# slot1.net
KiCad netlist of a schematic drawn in EAGLE
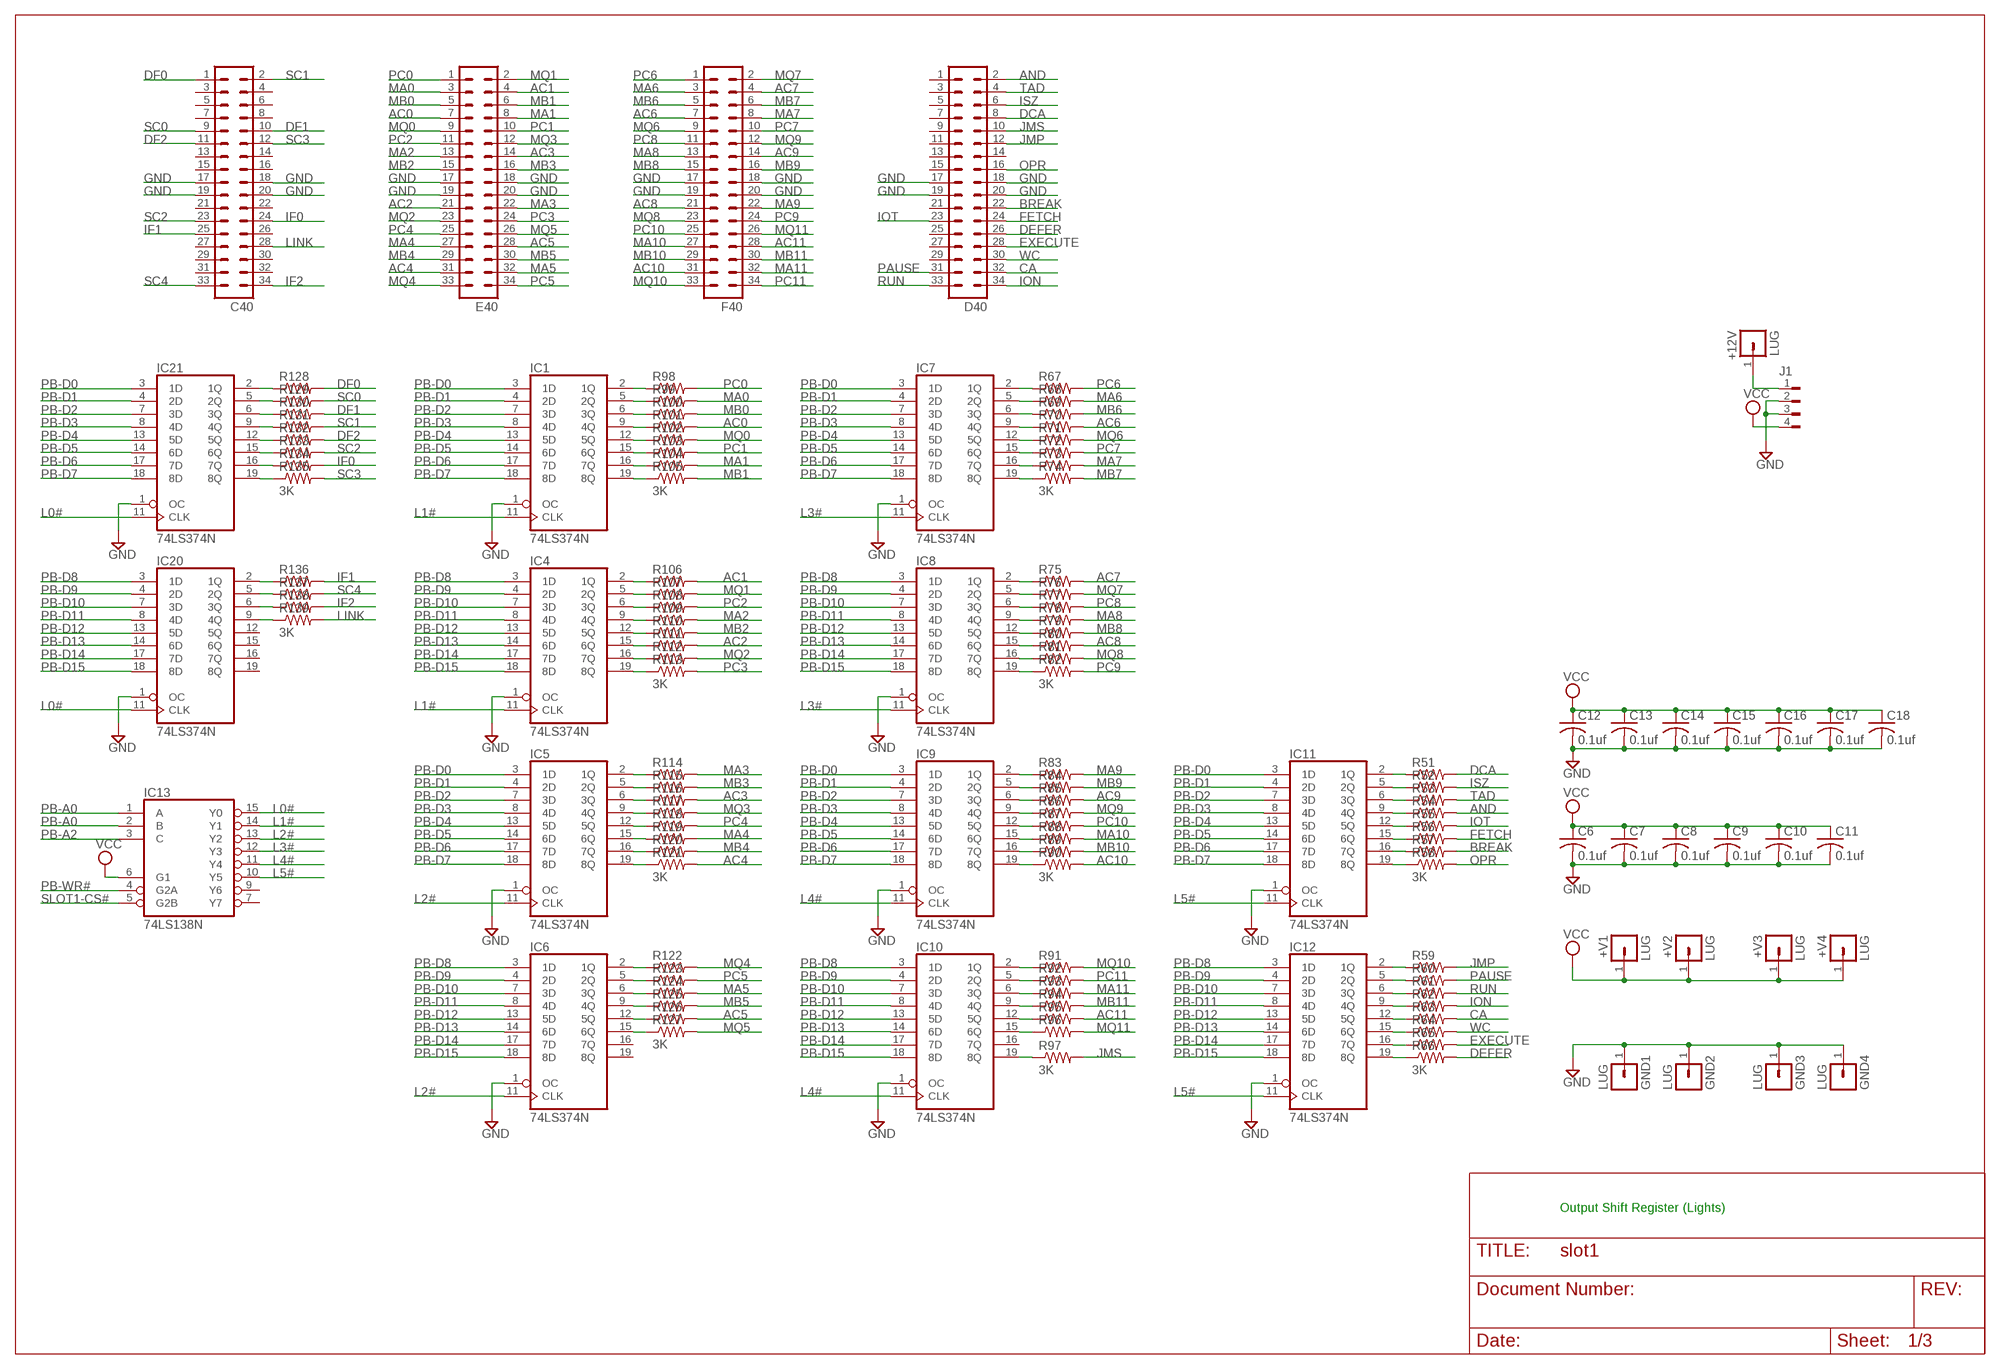
[diagram p0: schematic, sheet 1]
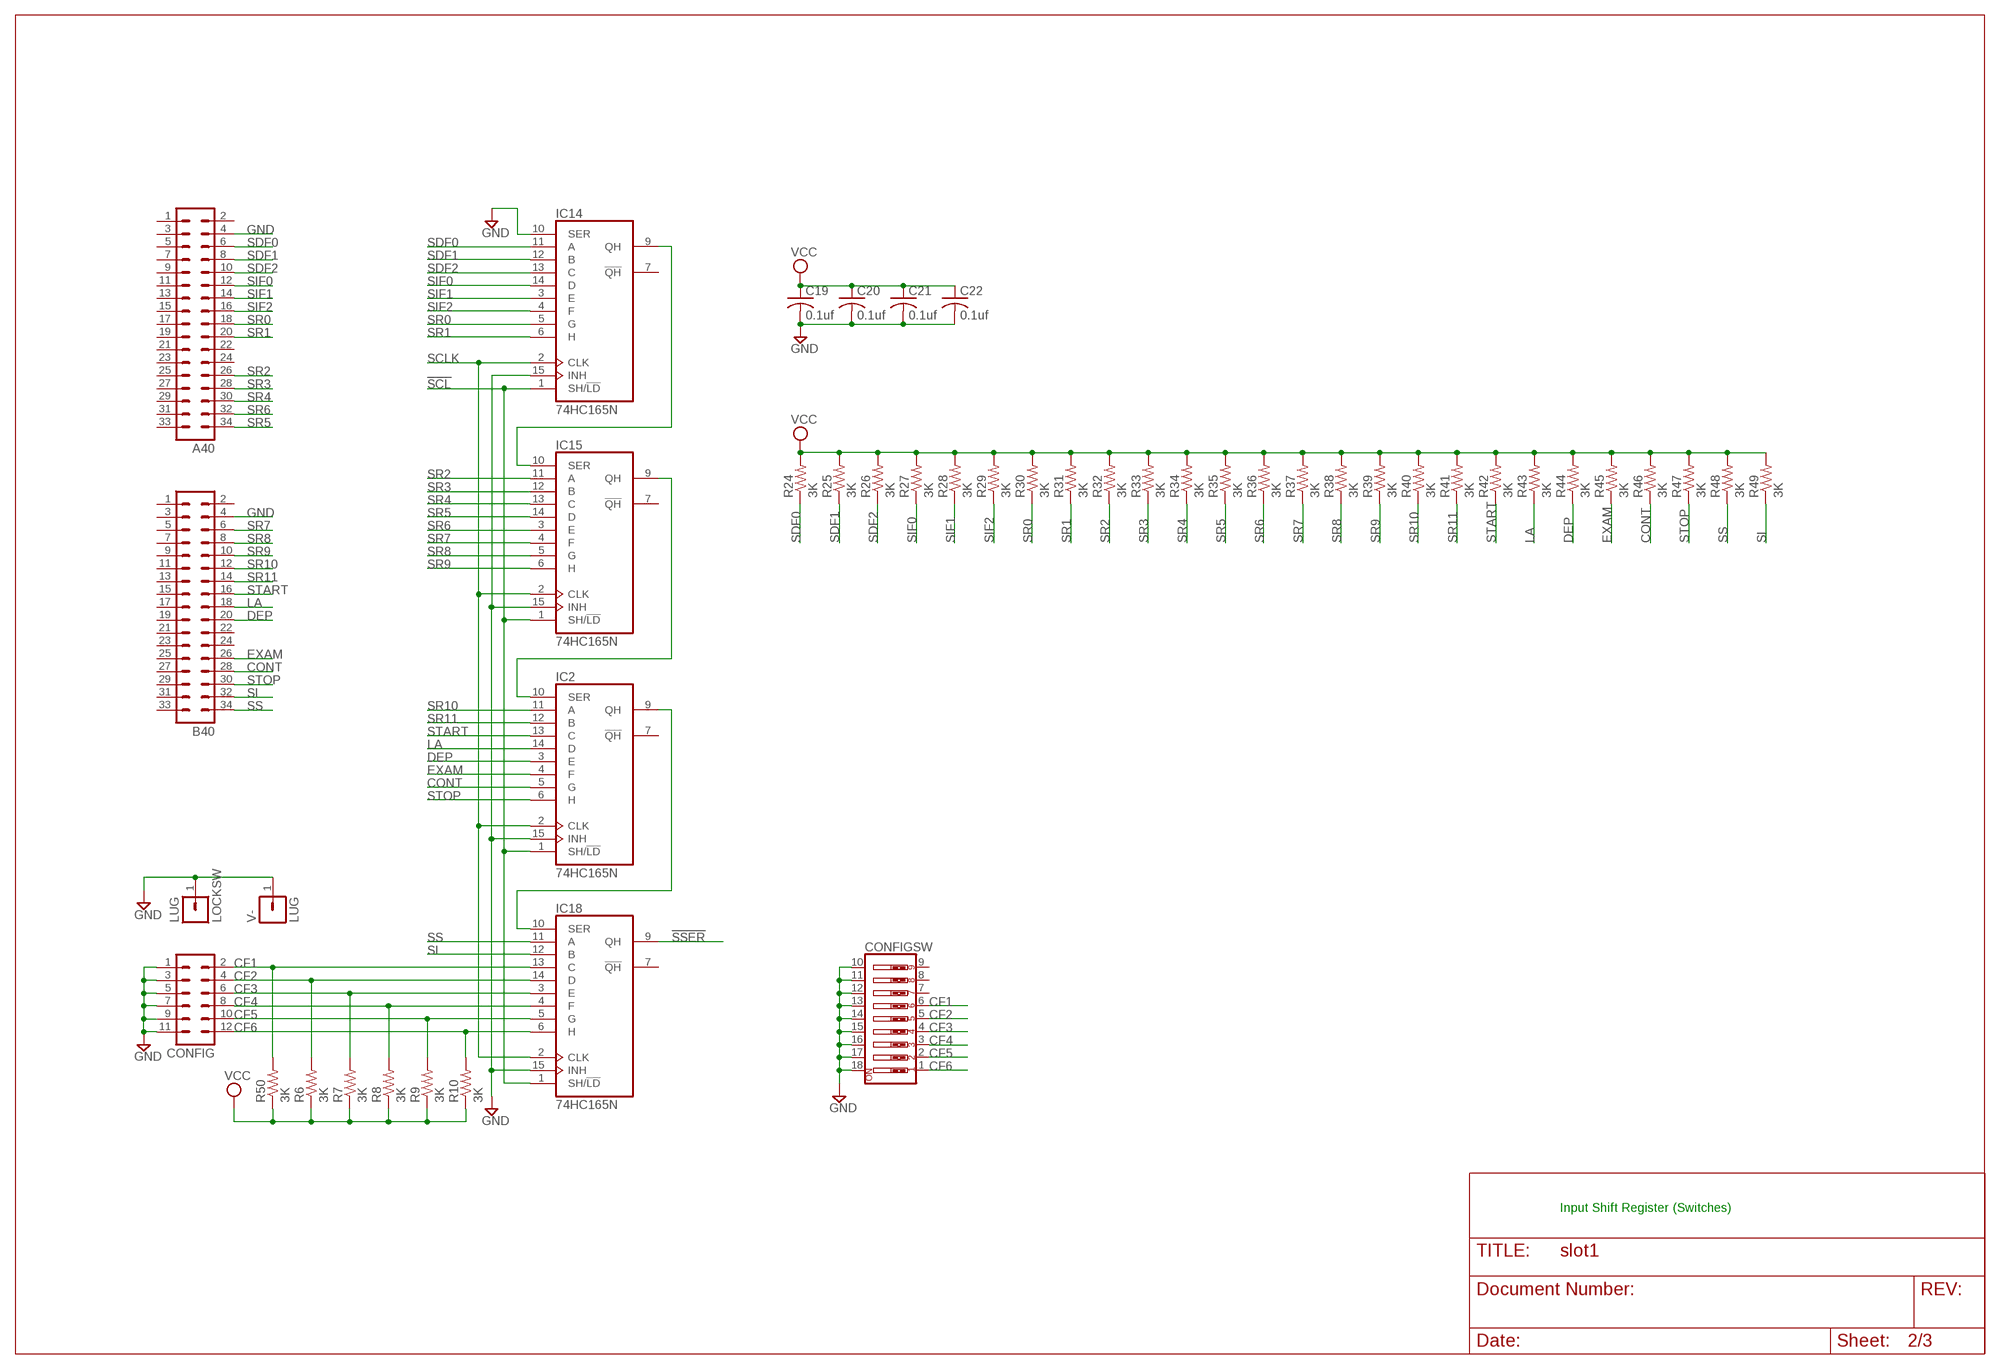
[diagram p1: schematic, sheet 2]
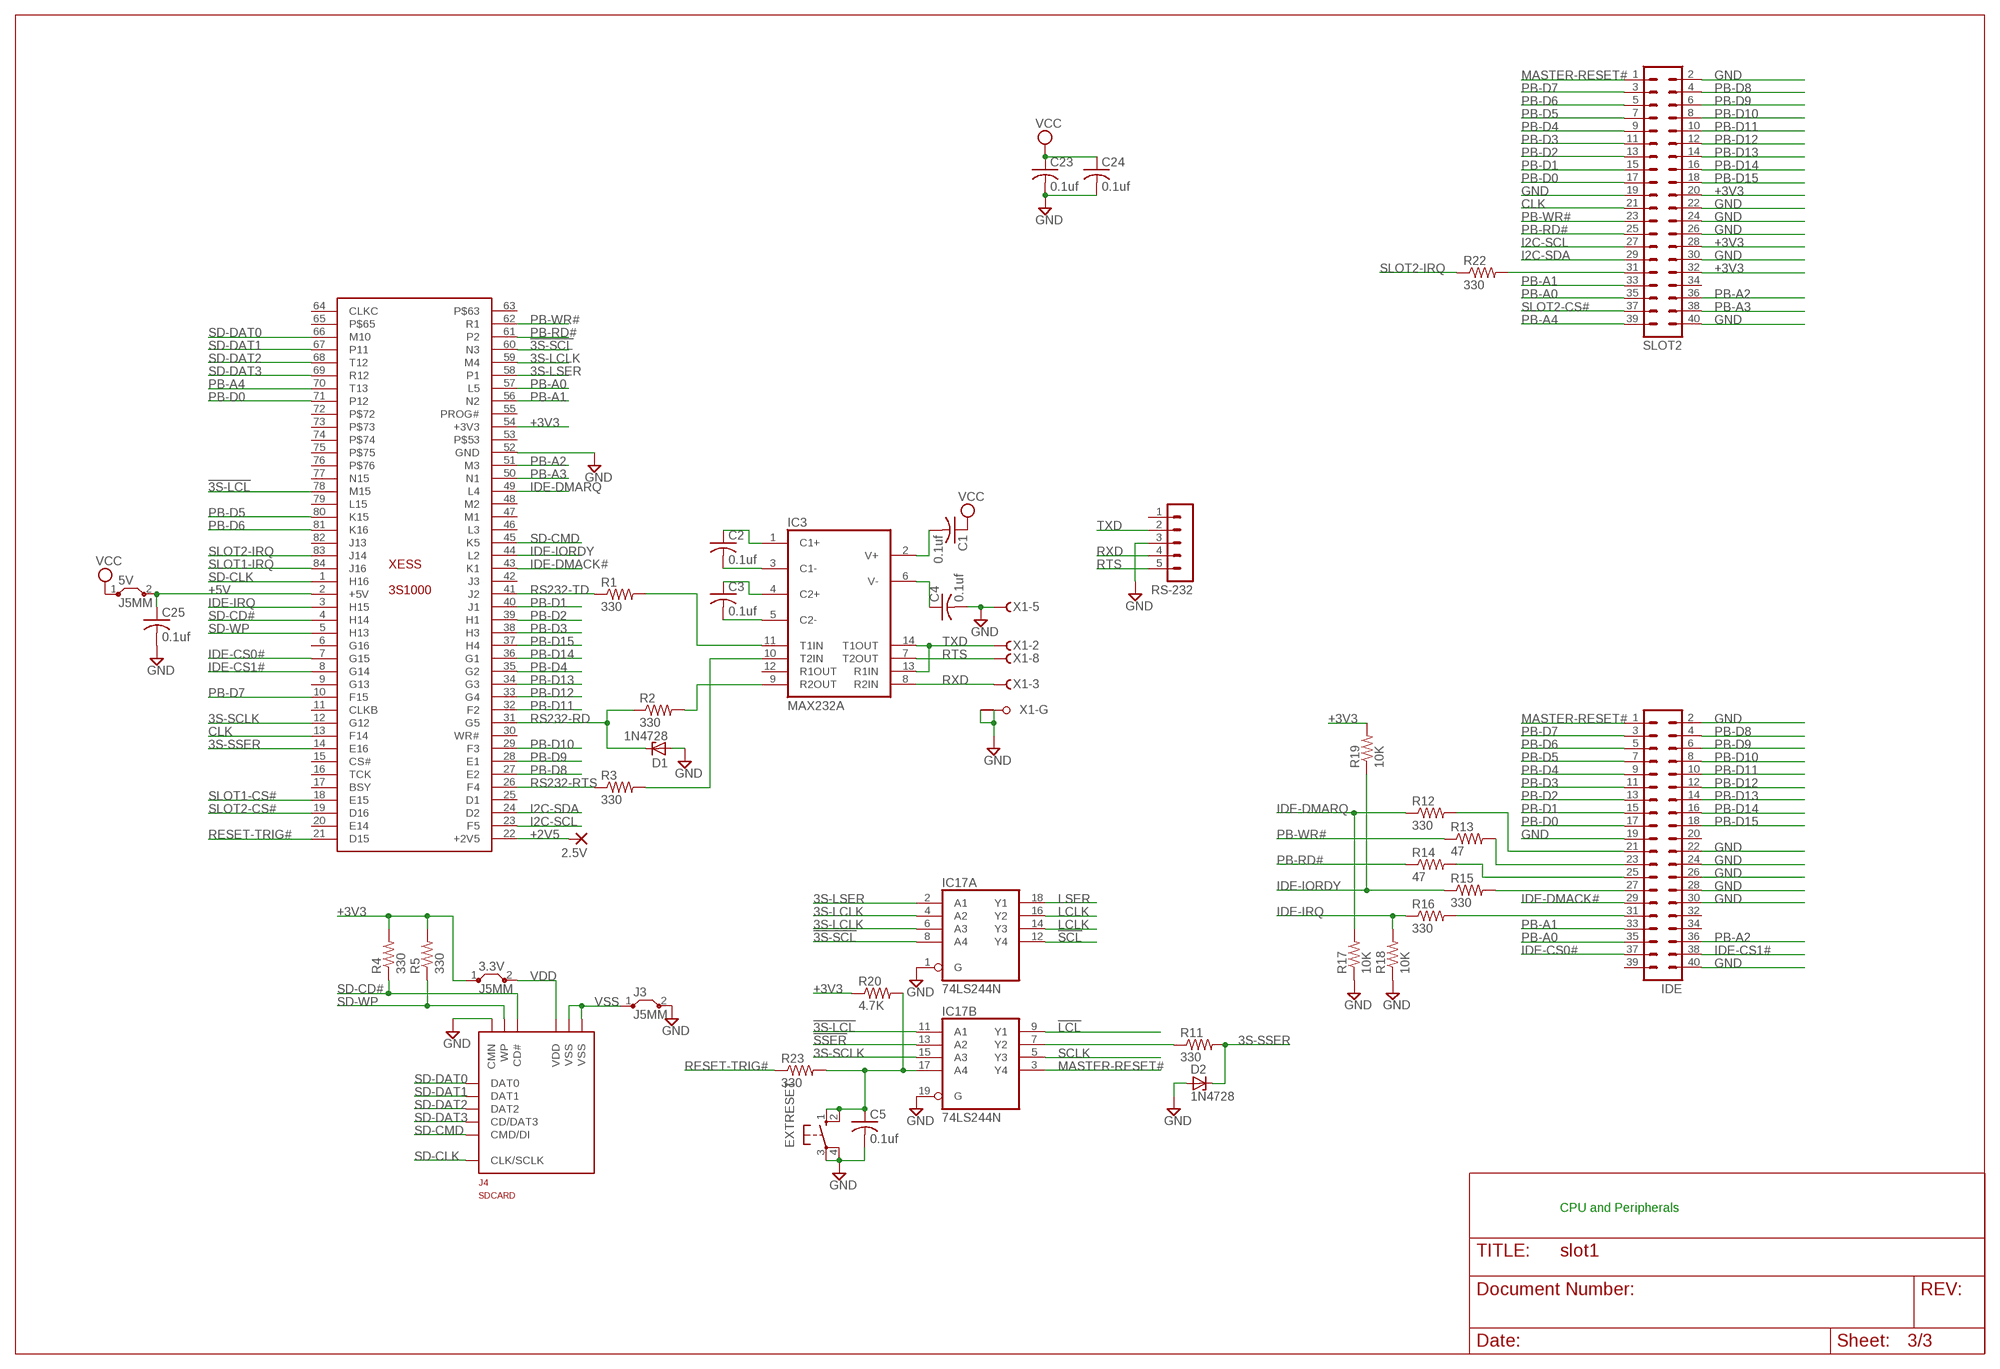
[diagram p2: schematic, sheet 3]

(export (version "E")
  (design (tool "Eeschema 10.0.6"))
  (components
    (comp (ref "2.5V")
      (value "1,6/0,8")
      (footprint "eagle-import:1,6_0,8")
      (libsource (lib "eagle-import") (part "1,6/0,8"))
    )
    (comp (ref "3.3V")
      (value "J5MM")
      (footprint "eagle-import:05")
      (libsource (lib "eagle-import") (part "J5MM"))
    )
    (comp (ref "5V")
      (value "J5MM")
      (footprint "eagle-import:05")
      (libsource (lib "eagle-import") (part "J5MM"))
    )
    (comp (ref "C1")
      (value "0.1uf")
      (footprint "eagle-import:C050-025X075")
      (libsource (lib "eagle-import") (part "C-US050-025X075"))
    )
    (comp (ref "C2")
      (value "0.1uf")
      (footprint "eagle-import:C050-025X075")
      (libsource (lib "eagle-import") (part "C-US050-025X075"))
    )
    (comp (ref "C3")
      (value "0.1uf")
      (footprint "eagle-import:C050-025X075")
      (libsource (lib "eagle-import") (part "C-US050-025X075"))
    )
    (comp (ref "C4")
      (value "0.1uf")
      (footprint "eagle-import:C050-025X075")
      (libsource (lib "eagle-import") (part "C-US050-025X075"))
    )
    (comp (ref "C5")
      (value "0.1uf")
      (footprint "eagle-import:C050-025X075")
      (libsource (lib "eagle-import") (part "C-US050-025X075"))
    )
    (comp (ref "C23")
      (value "0.1uf")
      (footprint "eagle-import:C050-025X075")
      (libsource (lib "eagle-import") (part "C-US050-025X075"))
    )
    (comp (ref "C24")
      (value "0.1uf")
      (footprint "eagle-import:C050-025X075")
      (libsource (lib "eagle-import") (part "C-US050-025X075"))
    )
    (comp (ref "C25")
      (value "0.1uf")
      (footprint "eagle-import:C050-025X075")
      (libsource (lib "eagle-import") (part "C-US050-025X075"))
    )
    (comp (ref "D1")
      (value "1N4728")
      (footprint "eagle-import:DO41Z10")
      (libsource (lib "eagle-import") (part "1N4728"))
    )
    (comp (ref "D2")
      (value "1N4728")
      (footprint "eagle-import:DO41Z10")
      (libsource (lib "eagle-import") (part "1N4728"))
    )
    (comp (ref "EXTRESET")
      (value "40-XX")
      (footprint "eagle-import:B3F-40XX")
      (fields (field (name "MF") "OMRON COMPONENTS USA") (field (name "MPN") "B3F-4000"))
      (libsource (lib "eagle-import") (part "40-XX"))
    )
    (comp (ref "IC3")
      (value "MAX232A")
      (footprint "eagle-import:DIL16")
      (fields (field (name "MF") "MAXIM") (field (name "MPN") "MAX232ACPE+"))
      (libsource (lib "eagle-import") (part "MAX232"))
    )
    (comp (ref "IC17")
      (value "74LS244N")
      (footprint "eagle-import:DIL20")
      (libsource (lib "eagle-import") (part "74244NLS"))
    )
    (comp (ref "IDE")
      (value "MA20-2")
      (footprint "eagle-import:MA20-2")
      (libsource (lib "eagle-import") (part "MA20-2"))
    )
    (comp (ref "J3")
      (value "J5MM")
      (footprint "eagle-import:05")
      (libsource (lib "eagle-import") (part "J5MM"))
    )
    (comp (ref "J4")
      (value "SDCARD")
      (footprint "eagle-import:SCDA5A")
      (libsource (lib "eagle-import") (part "SDCARD"))
    )
    (comp (ref "R1")
      (value "330")
      (footprint "eagle-import:0207_10")
      (libsource (lib "eagle-import") (part "R-US_0207/10"))
    )
    (comp (ref "R2")
      (value "330")
      (footprint "eagle-import:0207_10")
      (libsource (lib "eagle-import") (part "R-US_0207/10"))
    )
    (comp (ref "R3")
      (value "330")
      (footprint "eagle-import:0207_10")
      (libsource (lib "eagle-import") (part "R-US_0207/10"))
    )
    (comp (ref "R4")
      (value "330")
      (footprint "eagle-import:0207_10")
      (libsource (lib "eagle-import") (part "R-US_0207/10"))
    )
    (comp (ref "R5")
      (value "330")
      (footprint "eagle-import:0207_10")
      (libsource (lib "eagle-import") (part "R-US_0207/10"))
    )
    (comp (ref "R11")
      (value "330")
      (footprint "eagle-import:0207_10")
      (libsource (lib "eagle-import") (part "R-US_0207/10"))
    )
    (comp (ref "R12")
      (value "330")
      (footprint "eagle-import:0207_10")
      (libsource (lib "eagle-import") (part "R-US_0207/10"))
    )
    (comp (ref "R13")
      (value "47")
      (footprint "eagle-import:0207_10")
      (libsource (lib "eagle-import") (part "R-US_0207/10"))
    )
    (comp (ref "R14")
      (value "47")
      (footprint "eagle-import:0207_10")
      (libsource (lib "eagle-import") (part "R-US_0207/10"))
    )
    (comp (ref "R15")
      (value "330")
      (footprint "eagle-import:0207_10")
      (libsource (lib "eagle-import") (part "R-US_0207/10"))
    )
    (comp (ref "R16")
      (value "330")
      (footprint "eagle-import:0207_10")
      (libsource (lib "eagle-import") (part "R-US_0207/10"))
    )
    (comp (ref "R17")
      (value "10K")
      (footprint "eagle-import:0207_10")
      (libsource (lib "eagle-import") (part "R-US_0207/10"))
    )
    (comp (ref "R18")
      (value "10K")
      (footprint "eagle-import:0207_10")
      (libsource (lib "eagle-import") (part "R-US_0207/10"))
    )
    (comp (ref "R19")
      (value "10K")
      (footprint "eagle-import:0207_10")
      (libsource (lib "eagle-import") (part "R-US_0207/10"))
    )
    (comp (ref "R20")
      (value "4.7K")
      (footprint "eagle-import:0207_10")
      (libsource (lib "eagle-import") (part "R-US_0207/10"))
    )
    (comp (ref "R22")
      (value "330")
      (footprint "eagle-import:0207_10")
      (libsource (lib "eagle-import") (part "R-US_0207/10"))
    )
    (comp (ref "R23")
      (value "330")
      (footprint "eagle-import:0207_10")
      (libsource (lib "eagle-import") (part "R-US_0207/10"))
    )
    (comp (ref "RS-232")
      (value "MA05-1")
      (footprint "eagle-import:MA05-1")
      (libsource (lib "eagle-import") (part "MA05-1"))
    )
    (comp (ref "SLOT2")
      (value "MA20-2")
      (footprint "eagle-import:MA20-2")
      (libsource (lib "eagle-import") (part "MA20-2"))
    )
    (comp (ref "X1")
      (value "F09HPS")
      (footprint "eagle-import:F09HP")
      (libsource (lib "eagle-import") (part "F09HPS"))
    )
    (comp (ref "XESS")
      (value "3S1000")
      (footprint "eagle-import:3S1000")
      (libsource (lib "eagle-import") (part "3S1000"))
    )
    (comp (ref "+12V")
      (value "LUG")
      (footprint "eagle-import:SPADELUG")
      (libsource (lib "eagle-import") (part "LUG"))
    )
    (comp (ref "+V1")
      (value "LUG")
      (footprint "eagle-import:SPADELUG")
      (libsource (lib "eagle-import") (part "LUG"))
    )
    (comp (ref "+V2")
      (value "LUG")
      (footprint "eagle-import:SPADELUG")
      (libsource (lib "eagle-import") (part "LUG"))
    )
    (comp (ref "+V3")
      (value "LUG")
      (footprint "eagle-import:SPADELUG")
      (libsource (lib "eagle-import") (part "LUG"))
    )
    (comp (ref "+V4")
      (value "LUG")
      (footprint "eagle-import:SPADELUG")
      (libsource (lib "eagle-import") (part "LUG"))
    )
    (comp (ref "C6")
      (value "0.1uf")
      (footprint "eagle-import:C050-025X075")
      (libsource (lib "eagle-import") (part "C-US050-025X075"))
    )
    (comp (ref "C7")
      (value "0.1uf")
      (footprint "eagle-import:C050-025X075")
      (libsource (lib "eagle-import") (part "C-US050-025X075"))
    )
    (comp (ref "C8")
      (value "0.1uf")
      (footprint "eagle-import:C050-025X075")
      (libsource (lib "eagle-import") (part "C-US050-025X075"))
    )
    (comp (ref "C9")
      (value "0.1uf")
      (footprint "eagle-import:C050-025X075")
      (libsource (lib "eagle-import") (part "C-US050-025X075"))
    )
    (comp (ref "C10")
      (value "0.1uf")
      (footprint "eagle-import:C050-025X075")
      (libsource (lib "eagle-import") (part "C-US050-025X075"))
    )
    (comp (ref "C11")
      (value "0.1uf")
      (footprint "eagle-import:C050-025X075")
      (libsource (lib "eagle-import") (part "C-US050-025X075"))
    )
    (comp (ref "C12")
      (value "0.1uf")
      (footprint "eagle-import:C050-025X075")
      (libsource (lib "eagle-import") (part "C-US050-025X075"))
    )
    (comp (ref "C13")
      (value "0.1uf")
      (footprint "eagle-import:C050-025X075")
      (libsource (lib "eagle-import") (part "C-US050-025X075"))
    )
    (comp (ref "C14")
      (value "0.1uf")
      (footprint "eagle-import:C050-025X075")
      (libsource (lib "eagle-import") (part "C-US050-025X075"))
    )
    (comp (ref "C15")
      (value "0.1uf")
      (footprint "eagle-import:C050-025X075")
      (libsource (lib "eagle-import") (part "C-US050-025X075"))
    )
    (comp (ref "C16")
      (value "0.1uf")
      (footprint "eagle-import:C050-025X075")
      (libsource (lib "eagle-import") (part "C-US050-025X075"))
    )
    (comp (ref "C17")
      (value "0.1uf")
      (footprint "eagle-import:C050-025X075")
      (libsource (lib "eagle-import") (part "C-US050-025X075"))
    )
    (comp (ref "C18")
      (value "0.1uf")
      (footprint "eagle-import:C050-025X075")
      (libsource (lib "eagle-import") (part "C-US050-025X075"))
    )
    (comp (ref "C40")
      (value "MA17-2")
      (footprint "eagle-import:MA17-2")
      (libsource (lib "eagle-import") (part "MA17-2"))
    )
    (comp (ref "D40")
      (value "MA17-2")
      (footprint "eagle-import:MA17-2")
      (libsource (lib "eagle-import") (part "MA17-2"))
    )
    (comp (ref "E40")
      (value "MA17-2")
      (footprint "eagle-import:MA17-2")
      (libsource (lib "eagle-import") (part "MA17-2"))
    )
    (comp (ref "F40")
      (value "MA17-2")
      (footprint "eagle-import:MA17-2")
      (libsource (lib "eagle-import") (part "MA17-2"))
    )
    (comp (ref "GND1")
      (value "LUG")
      (footprint "eagle-import:SPADELUG")
      (libsource (lib "eagle-import") (part "LUG"))
    )
    (comp (ref "GND2")
      (value "LUG")
      (footprint "eagle-import:SPADELUG")
      (libsource (lib "eagle-import") (part "LUG"))
    )
    (comp (ref "GND3")
      (value "LUG")
      (footprint "eagle-import:SPADELUG")
      (libsource (lib "eagle-import") (part "LUG"))
    )
    (comp (ref "GND4")
      (value "LUG")
      (footprint "eagle-import:SPADELUG")
      (libsource (lib "eagle-import") (part "LUG"))
    )
    (comp (ref "IC1")
      (value "74LS374N")
      (footprint "eagle-import:DIL20")
      (libsource (lib "eagle-import") (part "74374NLS"))
    )
    (comp (ref "IC4")
      (value "74LS374N")
      (footprint "eagle-import:DIL20")
      (libsource (lib "eagle-import") (part "74374NLS"))
    )
    (comp (ref "IC5")
      (value "74LS374N")
      (footprint "eagle-import:DIL20")
      (libsource (lib "eagle-import") (part "74374NLS"))
    )
    (comp (ref "IC6")
      (value "74LS374N")
      (footprint "eagle-import:DIL20")
      (libsource (lib "eagle-import") (part "74374NLS"))
    )
    (comp (ref "IC7")
      (value "74LS374N")
      (footprint "eagle-import:DIL20")
      (libsource (lib "eagle-import") (part "74374NLS"))
    )
    (comp (ref "IC8")
      (value "74LS374N")
      (footprint "eagle-import:DIL20")
      (libsource (lib "eagle-import") (part "74374NLS"))
    )
    (comp (ref "IC9")
      (value "74LS374N")
      (footprint "eagle-import:DIL20")
      (libsource (lib "eagle-import") (part "74374NLS"))
    )
    (comp (ref "IC10")
      (value "74LS374N")
      (footprint "eagle-import:DIL20")
      (libsource (lib "eagle-import") (part "74374NLS"))
    )
    (comp (ref "IC11")
      (value "74LS374N")
      (footprint "eagle-import:DIL20")
      (libsource (lib "eagle-import") (part "74374NLS"))
    )
    (comp (ref "IC12")
      (value "74LS374N")
      (footprint "eagle-import:DIL20")
      (libsource (lib "eagle-import") (part "74374NLS"))
    )
    (comp (ref "IC13")
      (value "74LS138N")
      (footprint "eagle-import:DIL16")
      (libsource (lib "eagle-import") (part "74138NLS"))
    )
    (comp (ref "IC20")
      (value "74LS374N")
      (footprint "eagle-import:DIL20")
      (libsource (lib "eagle-import") (part "74374NLS"))
    )
    (comp (ref "IC21")
      (value "74LS374N")
      (footprint "eagle-import:DIL20")
      (libsource (lib "eagle-import") (part "74374NLS"))
    )
    (comp (ref "J1")
      (value "FLOPPY-4")
      (footprint "eagle-import:FLOPPY-4")
      (libsource (lib "eagle-import") (part "FLOPPY-4"))
    )
    (comp (ref "R51")
      (value "R-US_0207/10")
      (footprint "eagle-import:0207_10")
      (libsource (lib "eagle-import") (part "R-US_0207/10"))
    )
    (comp (ref "R52")
      (value "R-US_0207/10")
      (footprint "eagle-import:0207_10")
      (libsource (lib "eagle-import") (part "R-US_0207/10"))
    )
    (comp (ref "R53")
      (value "R-US_0207/10")
      (footprint "eagle-import:0207_10")
      (libsource (lib "eagle-import") (part "R-US_0207/10"))
    )
    (comp (ref "R54")
      (value "R-US_0207/10")
      (footprint "eagle-import:0207_10")
      (libsource (lib "eagle-import") (part "R-US_0207/10"))
    )
    (comp (ref "R55")
      (value "R-US_0207/10")
      (footprint "eagle-import:0207_10")
      (libsource (lib "eagle-import") (part "R-US_0207/10"))
    )
    (comp (ref "R56")
      (value "R-US_0207/10")
      (footprint "eagle-import:0207_10")
      (libsource (lib "eagle-import") (part "R-US_0207/10"))
    )
    (comp (ref "R57")
      (value "R-US_0207/10")
      (footprint "eagle-import:0207_10")
      (libsource (lib "eagle-import") (part "R-US_0207/10"))
    )
    (comp (ref "R58")
      (value "3K")
      (footprint "eagle-import:0207_10")
      (libsource (lib "eagle-import") (part "R-US_0207/10"))
    )
    (comp (ref "R59")
      (value "R-US_0207/10")
      (footprint "eagle-import:0207_10")
      (libsource (lib "eagle-import") (part "R-US_0207/10"))
    )
    (comp (ref "R60")
      (value "R-US_0207/10")
      (footprint "eagle-import:0207_10")
      (libsource (lib "eagle-import") (part "R-US_0207/10"))
    )
    (comp (ref "R61")
      (value "R-US_0207/10")
      (footprint "eagle-import:0207_10")
      (libsource (lib "eagle-import") (part "R-US_0207/10"))
    )
    (comp (ref "R62")
      (value "R-US_0207/10")
      (footprint "eagle-import:0207_10")
      (libsource (lib "eagle-import") (part "R-US_0207/10"))
    )
    (comp (ref "R63")
      (value "R-US_0207/10")
      (footprint "eagle-import:0207_10")
      (libsource (lib "eagle-import") (part "R-US_0207/10"))
    )
    (comp (ref "R64")
      (value "R-US_0207/10")
      (footprint "eagle-import:0207_10")
      (libsource (lib "eagle-import") (part "R-US_0207/10"))
    )
    (comp (ref "R65")
      (value "R-US_0207/10")
      (footprint "eagle-import:0207_10")
      (libsource (lib "eagle-import") (part "R-US_0207/10"))
    )
    (comp (ref "R66")
      (value "3K")
      (footprint "eagle-import:0207_10")
      (libsource (lib "eagle-import") (part "R-US_0207/10"))
    )
    (comp (ref "R67")
      (value "R-US_0207/10")
      (footprint "eagle-import:0207_10")
      (libsource (lib "eagle-import") (part "R-US_0207/10"))
    )
    (comp (ref "R68")
      (value "R-US_0207/10")
      (footprint "eagle-import:0207_10")
      (libsource (lib "eagle-import") (part "R-US_0207/10"))
    )
    (comp (ref "R69")
      (value "R-US_0207/10")
      (footprint "eagle-import:0207_10")
      (libsource (lib "eagle-import") (part "R-US_0207/10"))
    )
    (comp (ref "R70")
      (value "R-US_0207/10")
      (footprint "eagle-import:0207_10")
      (libsource (lib "eagle-import") (part "R-US_0207/10"))
    )
    (comp (ref "R71")
      (value "R-US_0207/10")
      (footprint "eagle-import:0207_10")
      (libsource (lib "eagle-import") (part "R-US_0207/10"))
    )
    (comp (ref "R72")
      (value "R-US_0207/10")
      (footprint "eagle-import:0207_10")
      (libsource (lib "eagle-import") (part "R-US_0207/10"))
    )
    (comp (ref "R73")
      (value "R-US_0207/10")
      (footprint "eagle-import:0207_10")
      (libsource (lib "eagle-import") (part "R-US_0207/10"))
    )
    (comp (ref "R74")
      (value "3K")
      (footprint "eagle-import:0207_10")
      (libsource (lib "eagle-import") (part "R-US_0207/10"))
    )
    (comp (ref "R75")
      (value "R-US_0207/10")
      (footprint "eagle-import:0207_10")
      (libsource (lib "eagle-import") (part "R-US_0207/10"))
    )
    (comp (ref "R76")
      (value "R-US_0207/10")
      (footprint "eagle-import:0207_10")
      (libsource (lib "eagle-import") (part "R-US_0207/10"))
    )
    (comp (ref "R77")
      (value "R-US_0207/10")
      (footprint "eagle-import:0207_10")
      (libsource (lib "eagle-import") (part "R-US_0207/10"))
    )
    (comp (ref "R78")
      (value "R-US_0207/10")
      (footprint "eagle-import:0207_10")
      (libsource (lib "eagle-import") (part "R-US_0207/10"))
    )
    (comp (ref "R79")
      (value "R-US_0207/10")
      (footprint "eagle-import:0207_10")
      (libsource (lib "eagle-import") (part "R-US_0207/10"))
    )
    (comp (ref "R80")
      (value "R-US_0207/10")
      (footprint "eagle-import:0207_10")
      (libsource (lib "eagle-import") (part "R-US_0207/10"))
    )
    (comp (ref "R81")
      (value "R-US_0207/10")
      (footprint "eagle-import:0207_10")
      (libsource (lib "eagle-import") (part "R-US_0207/10"))
    )
    (comp (ref "R82")
      (value "3K")
      (footprint "eagle-import:0207_10")
      (libsource (lib "eagle-import") (part "R-US_0207/10"))
    )
    (comp (ref "R83")
      (value "R-US_0207/10")
      (footprint "eagle-import:0207_10")
      (libsource (lib "eagle-import") (part "R-US_0207/10"))
    )
    (comp (ref "R84")
      (value "R-US_0207/10")
      (footprint "eagle-import:0207_10")
      (libsource (lib "eagle-import") (part "R-US_0207/10"))
    )
    (comp (ref "R85")
      (value "R-US_0207/10")
      (footprint "eagle-import:0207_10")
      (libsource (lib "eagle-import") (part "R-US_0207/10"))
    )
    (comp (ref "R86")
      (value "R-US_0207/10")
      (footprint "eagle-import:0207_10")
      (libsource (lib "eagle-import") (part "R-US_0207/10"))
    )
    (comp (ref "R87")
      (value "R-US_0207/10")
      (footprint "eagle-import:0207_10")
      (libsource (lib "eagle-import") (part "R-US_0207/10"))
    )
    (comp (ref "R88")
      (value "R-US_0207/10")
      (footprint "eagle-import:0207_10")
      (libsource (lib "eagle-import") (part "R-US_0207/10"))
    )
    (comp (ref "R89")
      (value "R-US_0207/10")
      (footprint "eagle-import:0207_10")
      (libsource (lib "eagle-import") (part "R-US_0207/10"))
    )
    (comp (ref "R90")
      (value "3K")
      (footprint "eagle-import:0207_10")
      (libsource (lib "eagle-import") (part "R-US_0207/10"))
    )
    (comp (ref "R91")
      (value "R-US_0207/10")
      (footprint "eagle-import:0207_10")
      (libsource (lib "eagle-import") (part "R-US_0207/10"))
    )
    (comp (ref "R92")
      (value "R-US_0207/10")
      (footprint "eagle-import:0207_10")
      (libsource (lib "eagle-import") (part "R-US_0207/10"))
    )
    (comp (ref "R93")
      (value "R-US_0207/10")
      (footprint "eagle-import:0207_10")
      (libsource (lib "eagle-import") (part "R-US_0207/10"))
    )
    (comp (ref "R94")
      (value "R-US_0207/10")
      (footprint "eagle-import:0207_10")
      (libsource (lib "eagle-import") (part "R-US_0207/10"))
    )
    (comp (ref "R95")
      (value "R-US_0207/10")
      (footprint "eagle-import:0207_10")
      (libsource (lib "eagle-import") (part "R-US_0207/10"))
    )
    (comp (ref "R96")
      (value "R-US_0207/10")
      (footprint "eagle-import:0207_10")
      (libsource (lib "eagle-import") (part "R-US_0207/10"))
    )
    (comp (ref "R97")
      (value "3K")
      (footprint "eagle-import:0207_10")
      (libsource (lib "eagle-import") (part "R-US_0207/10"))
    )
    (comp (ref "R98")
      (value "R-US_0207/10")
      (footprint "eagle-import:0207_10")
      (libsource (lib "eagle-import") (part "R-US_0207/10"))
    )
    (comp (ref "R99")
      (value "R-US_0207/10")
      (footprint "eagle-import:0207_10")
      (libsource (lib "eagle-import") (part "R-US_0207/10"))
    )
    (comp (ref "R100")
      (value "R-US_0207/10")
      (footprint "eagle-import:0207_10")
      (libsource (lib "eagle-import") (part "R-US_0207/10"))
    )
    (comp (ref "R101")
      (value "R-US_0207/10")
      (footprint "eagle-import:0207_10")
      (libsource (lib "eagle-import") (part "R-US_0207/10"))
    )
    (comp (ref "R102")
      (value "R-US_0207/10")
      (footprint "eagle-import:0207_10")
      (libsource (lib "eagle-import") (part "R-US_0207/10"))
    )
    (comp (ref "R103")
      (value "R-US_0207/10")
      (footprint "eagle-import:0207_10")
      (libsource (lib "eagle-import") (part "R-US_0207/10"))
    )
    (comp (ref "R104")
      (value "R-US_0207/10")
      (footprint "eagle-import:0207_10")
      (libsource (lib "eagle-import") (part "R-US_0207/10"))
    )
    (comp (ref "R105")
      (value "3K")
      (footprint "eagle-import:0207_10")
      (libsource (lib "eagle-import") (part "R-US_0207/10"))
    )
    (comp (ref "R106")
      (value "R-US_0207/10")
      (footprint "eagle-import:0207_10")
      (libsource (lib "eagle-import") (part "R-US_0207/10"))
    )
    (comp (ref "R107")
      (value "R-US_0207/10")
      (footprint "eagle-import:0207_10")
      (libsource (lib "eagle-import") (part "R-US_0207/10"))
    )
    (comp (ref "R108")
      (value "R-US_0207/10")
      (footprint "eagle-import:0207_10")
      (libsource (lib "eagle-import") (part "R-US_0207/10"))
    )
    (comp (ref "R109")
      (value "R-US_0207/10")
      (footprint "eagle-import:0207_10")
      (libsource (lib "eagle-import") (part "R-US_0207/10"))
    )
    (comp (ref "R110")
      (value "R-US_0207/10")
      (footprint "eagle-import:0207_10")
      (libsource (lib "eagle-import") (part "R-US_0207/10"))
    )
    (comp (ref "R111")
      (value "R-US_0207/10")
      (footprint "eagle-import:0207_10")
      (libsource (lib "eagle-import") (part "R-US_0207/10"))
    )
    (comp (ref "R112")
      (value "R-US_0207/10")
      (footprint "eagle-import:0207_10")
      (libsource (lib "eagle-import") (part "R-US_0207/10"))
    )
    (comp (ref "R113")
      (value "3K")
      (footprint "eagle-import:0207_10")
      (libsource (lib "eagle-import") (part "R-US_0207/10"))
    )
    (comp (ref "R114")
      (value "R-US_0207/10")
      (footprint "eagle-import:0207_10")
      (libsource (lib "eagle-import") (part "R-US_0207/10"))
    )
    (comp (ref "R115")
      (value "R-US_0207/10")
      (footprint "eagle-import:0207_10")
      (libsource (lib "eagle-import") (part "R-US_0207/10"))
    )
    (comp (ref "R116")
      (value "R-US_0207/10")
      (footprint "eagle-import:0207_10")
      (libsource (lib "eagle-import") (part "R-US_0207/10"))
    )
    (comp (ref "R117")
      (value "R-US_0207/10")
      (footprint "eagle-import:0207_10")
      (libsource (lib "eagle-import") (part "R-US_0207/10"))
    )
    (comp (ref "R118")
      (value "R-US_0207/10")
      (footprint "eagle-import:0207_10")
      (libsource (lib "eagle-import") (part "R-US_0207/10"))
    )
    (comp (ref "R119")
      (value "R-US_0207/10")
      (footprint "eagle-import:0207_10")
      (libsource (lib "eagle-import") (part "R-US_0207/10"))
    )
    (comp (ref "R120")
      (value "R-US_0207/10")
      (footprint "eagle-import:0207_10")
      (libsource (lib "eagle-import") (part "R-US_0207/10"))
    )
    (comp (ref "R121")
      (value "3K")
      (footprint "eagle-import:0207_10")
      (libsource (lib "eagle-import") (part "R-US_0207/10"))
    )
    (comp (ref "R122")
      (value "R-US_0207/10")
      (footprint "eagle-import:0207_10")
      (libsource (lib "eagle-import") (part "R-US_0207/10"))
    )
    (comp (ref "R123")
      (value "R-US_0207/10")
      (footprint "eagle-import:0207_10")
      (libsource (lib "eagle-import") (part "R-US_0207/10"))
    )
    (comp (ref "R124")
      (value "R-US_0207/10")
      (footprint "eagle-import:0207_10")
      (libsource (lib "eagle-import") (part "R-US_0207/10"))
    )
    (comp (ref "R125")
      (value "R-US_0207/10")
      (footprint "eagle-import:0207_10")
      (libsource (lib "eagle-import") (part "R-US_0207/10"))
    )
    (comp (ref "R126")
      (value "R-US_0207/10")
      (footprint "eagle-import:0207_10")
      (libsource (lib "eagle-import") (part "R-US_0207/10"))
    )
    (comp (ref "R127")
      (value "3K")
      (footprint "eagle-import:0207_10")
      (libsource (lib "eagle-import") (part "R-US_0207/10"))
    )
    (comp (ref "R128")
      (value "R-US_0207/10")
      (footprint "eagle-import:0207_10")
      (libsource (lib "eagle-import") (part "R-US_0207/10"))
    )
    (comp (ref "R129")
      (value "R-US_0207/10")
      (footprint "eagle-import:0207_10")
      (libsource (lib "eagle-import") (part "R-US_0207/10"))
    )
    (comp (ref "R130")
      (value "R-US_0207/10")
      (footprint "eagle-import:0207_10")
      (libsource (lib "eagle-import") (part "R-US_0207/10"))
    )
    (comp (ref "R131")
      (value "R-US_0207/10")
      (footprint "eagle-import:0207_10")
      (libsource (lib "eagle-import") (part "R-US_0207/10"))
    )
    (comp (ref "R132")
      (value "R-US_0207/10")
      (footprint "eagle-import:0207_10")
      (libsource (lib "eagle-import") (part "R-US_0207/10"))
    )
    (comp (ref "R133")
      (value "R-US_0207/10")
      (footprint "eagle-import:0207_10")
      (libsource (lib "eagle-import") (part "R-US_0207/10"))
    )
    (comp (ref "R134")
      (value "R-US_0207/10")
      (footprint "eagle-import:0207_10")
      (libsource (lib "eagle-import") (part "R-US_0207/10"))
    )
    (comp (ref "R135")
      (value "3K")
      (footprint "eagle-import:0207_10")
      (libsource (lib "eagle-import") (part "R-US_0207/10"))
    )
    (comp (ref "R136")
      (value "R-US_0207/10")
      (footprint "eagle-import:0207_10")
      (libsource (lib "eagle-import") (part "R-US_0207/10"))
    )
    (comp (ref "R137")
      (value "R-US_0207/10")
      (footprint "eagle-import:0207_10")
      (libsource (lib "eagle-import") (part "R-US_0207/10"))
    )
    (comp (ref "R138")
      (value "R-US_0207/10")
      (footprint "eagle-import:0207_10")
      (libsource (lib "eagle-import") (part "R-US_0207/10"))
    )
    (comp (ref "R139")
      (value "3K")
      (footprint "eagle-import:0207_10")
      (libsource (lib "eagle-import") (part "R-US_0207/10"))
    )
    (comp (ref "A40")
      (value "MA17-2")
      (footprint "eagle-import:MA17-2")
      (libsource (lib "eagle-import") (part "MA17-2"))
    )
    (comp (ref "B40")
      (value "MA17-2")
      (footprint "eagle-import:MA17-2")
      (libsource (lib "eagle-import") (part "MA17-2"))
    )
    (comp (ref "C19")
      (value "0.1uf")
      (footprint "eagle-import:C050-025X075")
      (libsource (lib "eagle-import") (part "C-US050-025X075"))
    )
    (comp (ref "C20")
      (value "0.1uf")
      (footprint "eagle-import:C050-025X075")
      (libsource (lib "eagle-import") (part "C-US050-025X075"))
    )
    (comp (ref "C21")
      (value "0.1uf")
      (footprint "eagle-import:C050-025X075")
      (libsource (lib "eagle-import") (part "C-US050-025X075"))
    )
    (comp (ref "C22")
      (value "0.1uf")
      (footprint "eagle-import:C050-025X075")
      (libsource (lib "eagle-import") (part "C-US050-025X075"))
    )
    (comp (ref "CONFIG")
      (value "MA06-2")
      (footprint "eagle-import:MA06-2")
      (libsource (lib "eagle-import") (part "MA06-2"))
    )
    (comp (ref "CONFIGSW")
      (value "SW_DIP-9")
      (footprint "eagle-import:EDG-09")
      (libsource (lib "eagle-import") (part "SW_DIP-9"))
    )
    (comp (ref "IC2")
      (value "74HC165N")
      (footprint "eagle-import:DIL16")
      (libsource (lib "eagle-import") (part "74165NLS"))
    )
    (comp (ref "IC14")
      (value "74HC165N")
      (footprint "eagle-import:DIL16")
      (libsource (lib "eagle-import") (part "74165NLS"))
    )
    (comp (ref "IC15")
      (value "74HC165N")
      (footprint "eagle-import:DIL16")
      (libsource (lib "eagle-import") (part "74165NLS"))
    )
    (comp (ref "IC18")
      (value "74HC165N")
      (footprint "eagle-import:DIL16")
      (libsource (lib "eagle-import") (part "74165NLS"))
    )
    (comp (ref "LOCKSW")
      (value "LUG")
      (footprint "eagle-import:SPADELUG")
      (libsource (lib "eagle-import") (part "LUG"))
    )
    (comp (ref "R6")
      (value "3K")
      (footprint "eagle-import:0207_10")
      (libsource (lib "eagle-import") (part "R-US_0207/10"))
    )
    (comp (ref "R7")
      (value "3K")
      (footprint "eagle-import:0207_10")
      (libsource (lib "eagle-import") (part "R-US_0207/10"))
    )
    (comp (ref "R8")
      (value "3K")
      (footprint "eagle-import:0207_10")
      (libsource (lib "eagle-import") (part "R-US_0207/10"))
    )
    (comp (ref "R9")
      (value "3K")
      (footprint "eagle-import:0207_10")
      (libsource (lib "eagle-import") (part "R-US_0207/10"))
    )
    (comp (ref "R10")
      (value "3K")
      (footprint "eagle-import:0207_10")
      (libsource (lib "eagle-import") (part "R-US_0207/10"))
    )
    (comp (ref "R24")
      (value "3K")
      (footprint "eagle-import:0207_10")
      (libsource (lib "eagle-import") (part "R-US_0207/10"))
    )
    (comp (ref "R25")
      (value "3K")
      (footprint "eagle-import:0207_10")
      (libsource (lib "eagle-import") (part "R-US_0207/10"))
    )
    (comp (ref "R26")
      (value "3K")
      (footprint "eagle-import:0207_10")
      (libsource (lib "eagle-import") (part "R-US_0207/10"))
    )
    (comp (ref "R27")
      (value "3K")
      (footprint "eagle-import:0207_10")
      (libsource (lib "eagle-import") (part "R-US_0207/10"))
    )
    (comp (ref "R28")
      (value "3K")
      (footprint "eagle-import:0207_10")
      (libsource (lib "eagle-import") (part "R-US_0207/10"))
    )
    (comp (ref "R29")
      (value "3K")
      (footprint "eagle-import:0207_10")
      (libsource (lib "eagle-import") (part "R-US_0207/10"))
    )
    (comp (ref "R30")
      (value "3K")
      (footprint "eagle-import:0207_10")
      (libsource (lib "eagle-import") (part "R-US_0207/10"))
    )
    (comp (ref "R31")
      (value "3K")
      (footprint "eagle-import:0207_10")
      (libsource (lib "eagle-import") (part "R-US_0207/10"))
    )
    (comp (ref "R32")
      (value "3K")
      (footprint "eagle-import:0207_10")
      (libsource (lib "eagle-import") (part "R-US_0207/10"))
    )
    (comp (ref "R33")
      (value "3K")
      (footprint "eagle-import:0207_10")
      (libsource (lib "eagle-import") (part "R-US_0207/10"))
    )
    (comp (ref "R34")
      (value "3K")
      (footprint "eagle-import:0207_10")
      (libsource (lib "eagle-import") (part "R-US_0207/10"))
    )
    (comp (ref "R35")
      (value "3K")
      (footprint "eagle-import:0207_10")
      (libsource (lib "eagle-import") (part "R-US_0207/10"))
    )
    (comp (ref "R36")
      (value "3K")
      (footprint "eagle-import:0207_10")
      (libsource (lib "eagle-import") (part "R-US_0207/10"))
    )
    (comp (ref "R37")
      (value "3K")
      (footprint "eagle-import:0207_10")
      (libsource (lib "eagle-import") (part "R-US_0207/10"))
    )
    (comp (ref "R38")
      (value "3K")
      (footprint "eagle-import:0207_10")
      (libsource (lib "eagle-import") (part "R-US_0207/10"))
    )
    (comp (ref "R39")
      (value "3K")
      (footprint "eagle-import:0207_10")
      (libsource (lib "eagle-import") (part "R-US_0207/10"))
    )
    (comp (ref "R40")
      (value "3K")
      (footprint "eagle-import:0207_10")
      (libsource (lib "eagle-import") (part "R-US_0207/10"))
    )
    (comp (ref "R41")
      (value "3K")
      (footprint "eagle-import:0207_10")
      (libsource (lib "eagle-import") (part "R-US_0207/10"))
    )
    (comp (ref "R42")
      (value "3K")
      (footprint "eagle-import:0207_10")
      (libsource (lib "eagle-import") (part "R-US_0207/10"))
    )
    (comp (ref "R43")
      (value "3K")
      (footprint "eagle-import:0207_10")
      (libsource (lib "eagle-import") (part "R-US_0207/10"))
    )
    (comp (ref "R44")
      (value "3K")
      (footprint "eagle-import:0207_10")
      (libsource (lib "eagle-import") (part "R-US_0207/10"))
    )
    (comp (ref "R45")
      (value "3K")
      (footprint "eagle-import:0207_10")
      (libsource (lib "eagle-import") (part "R-US_0207/10"))
    )
    (comp (ref "R46")
      (value "3K")
      (footprint "eagle-import:0207_10")
      (libsource (lib "eagle-import") (part "R-US_0207/10"))
    )
    (comp (ref "R47")
      (value "3K")
      (footprint "eagle-import:0207_10")
      (libsource (lib "eagle-import") (part "R-US_0207/10"))
    )
    (comp (ref "R48")
      (value "3K")
      (footprint "eagle-import:0207_10")
      (libsource (lib "eagle-import") (part "R-US_0207/10"))
    )
    (comp (ref "R49")
      (value "3K")
      (footprint "eagle-import:0207_10")
      (libsource (lib "eagle-import") (part "R-US_0207/10"))
    )
    (comp (ref "R50")
      (value "3K")
      (footprint "eagle-import:0207_10")
      (libsource (lib "eagle-import") (part "R-US_0207/10"))
    )
    (comp (ref "V-")
      (value "LUG")
      (footprint "eagle-import:SPADELUG")
      (libsource (lib "eagle-import") (part "LUG"))
    )
  )
  (nets
    (net (code "1") (name "+2V5") (class "Default")
      (node (ref "2.5V") (pin "1") (pinfunction "P_1") (pintype "passive"))
      (node (ref "XESS") (pin "22") (pinfunction "+2V5_22") (pintype "power_in"))
    )
    (net (code "2") (name "+3V3") (class "Default")
      (node (ref "3.3V") (pin "1") (pinfunction "1_1") (pintype "passive"))
      (node (ref "R19") (pin "2") (pinfunction "2_2") (pintype "passive"))
      (node (ref "R20") (pin "1") (pinfunction "1_1") (pintype "passive"))
      (node (ref "R4") (pin "2") (pinfunction "2_2") (pintype "passive"))
      (node (ref "R5") (pin "2") (pinfunction "2_2") (pintype "passive"))
      (node (ref "SLOT2") (pin "20") (pinfunction "20_20") (pintype "passive"))
      (node (ref "SLOT2") (pin "28") (pinfunction "28_28") (pintype "passive"))
      (node (ref "SLOT2") (pin "32") (pinfunction "32_32") (pintype "passive"))
      (node (ref "XESS") (pin "54") (pinfunction "+3V3_54") (pintype "power_in"))
    )
    (net (code "3") (name "+5V") (class "Default")
      (node (ref "5V") (pin "2") (pinfunction "2_2") (pintype "passive"))
      (node (ref "C25") (pin "1") (pinfunction "1_1") (pintype "passive"))
      (node (ref "XESS") (pin "2") (pinfunction "+5V_2") (pintype "power_in"))
    )
    (net (code "4") (name "3S-LCLK") (class "Default")
      (node (ref "IC17") (pin "4") (pinfunction "A2_4") (pintype "input"))
      (node (ref "IC17") (pin "6") (pinfunction "A3_6") (pintype "input"))
      (node (ref "XESS") (pin "59") (pinfunction "M4_59") (pintype "bidirectional"))
    )
    (net (code "5") (name "3S-LSER") (class "Default")
      (node (ref "IC17") (pin "2") (pinfunction "A1_2") (pintype "input"))
      (node (ref "XESS") (pin "58") (pinfunction "P1_58") (pintype "bidirectional"))
    )
    (net (code "6") (name "3S-SCLK") (class "Default")
      (node (ref "IC17") (pin "15") (pinfunction "A3_15") (pintype "input"))
      (node (ref "XESS") (pin "12") (pinfunction "G12_12") (pintype "bidirectional"))
    )
    (net (code "7") (name "3S-SSER") (class "Default")
      (node (ref "D2") (pin "C") (pinfunction "C_C") (pintype "passive"))
      (node (ref "R11") (pin "2") (pinfunction "2_2") (pintype "passive"))
      (node (ref "XESS") (pin "14") (pinfunction "E16_14") (pintype "bidirectional"))
    )
    (net (code "8") (name "AC0") (class "Default")
      (node (ref "E40") (pin "7") (pinfunction "7_7") (pintype "passive"))
      (node (ref "R101") (pin "2") (pinfunction "2_2") (pintype "passive"))
    )
    (net (code "9") (name "AC1") (class "Default")
      (node (ref "E40") (pin "4") (pinfunction "4_4") (pintype "passive"))
      (node (ref "R106") (pin "2") (pinfunction "2_2") (pintype "passive"))
    )
    (net (code "10") (name "AC2") (class "Default")
      (node (ref "E40") (pin "21") (pinfunction "21_21") (pintype "passive"))
      (node (ref "R111") (pin "2") (pinfunction "2_2") (pintype "passive"))
    )
    (net (code "11") (name "AC3") (class "Default")
      (node (ref "E40") (pin "14") (pinfunction "14_14") (pintype "passive"))
      (node (ref "R116") (pin "2") (pinfunction "2_2") (pintype "passive"))
    )
    (net (code "12") (name "AC4") (class "Default")
      (node (ref "E40") (pin "31") (pinfunction "31_31") (pintype "passive"))
      (node (ref "R121") (pin "2") (pinfunction "2_2") (pintype "passive"))
    )
    (net (code "13") (name "AC5") (class "Default")
      (node (ref "E40") (pin "28") (pinfunction "28_28") (pintype "passive"))
      (node (ref "R126") (pin "2") (pinfunction "2_2") (pintype "passive"))
    )
    (net (code "14") (name "AC6") (class "Default")
      (node (ref "F40") (pin "7") (pinfunction "7_7") (pintype "passive"))
      (node (ref "R70") (pin "2") (pinfunction "2_2") (pintype "passive"))
    )
    (net (code "15") (name "AC7") (class "Default")
      (node (ref "F40") (pin "4") (pinfunction "4_4") (pintype "passive"))
      (node (ref "R75") (pin "2") (pinfunction "2_2") (pintype "passive"))
    )
    (net (code "16") (name "AC8") (class "Default")
      (node (ref "F40") (pin "21") (pinfunction "21_21") (pintype "passive"))
      (node (ref "R80") (pin "2") (pinfunction "2_2") (pintype "passive"))
    )
    (net (code "17") (name "AC9") (class "Default")
      (node (ref "F40") (pin "14") (pinfunction "14_14") (pintype "passive"))
      (node (ref "R85") (pin "2") (pinfunction "2_2") (pintype "passive"))
    )
    (net (code "18") (name "AC10") (class "Default")
      (node (ref "F40") (pin "31") (pinfunction "31_31") (pintype "passive"))
      (node (ref "R90") (pin "2") (pinfunction "2_2") (pintype "passive"))
    )
    (net (code "19") (name "AC11") (class "Default")
      (node (ref "F40") (pin "28") (pinfunction "28_28") (pintype "passive"))
      (node (ref "R95") (pin "2") (pinfunction "2_2") (pintype "passive"))
    )
    (net (code "20") (name "AND") (class "Default")
      (node (ref "D40") (pin "2") (pinfunction "2_2") (pintype "passive"))
      (node (ref "R54") (pin "2") (pinfunction "2_2") (pintype "passive"))
    )
    (net (code "21") (name "BREAK") (class "Default")
      (node (ref "D40") (pin "22") (pinfunction "22_22") (pintype "passive"))
      (node (ref "R57") (pin "2") (pinfunction "2_2") (pintype "passive"))
    )
    (net (code "22") (name "CA") (class "Default")
      (node (ref "D40") (pin "32") (pinfunction "32_32") (pintype "passive"))
      (node (ref "R63") (pin "2") (pinfunction "2_2") (pintype "passive"))
    )
    (net (code "23") (name "CF1") (class "Default")
      (node (ref "CONFIG") (pin "2") (pinfunction "2_2") (pintype "passive"))
      (node (ref "CONFIGSW") (pin "6") (pinfunction "6_6") (pintype "passive"))
      (node (ref "IC18") (pin "13") (pinfunction "C_13") (pintype "input"))
      (node (ref "R50") (pin "2") (pinfunction "2_2") (pintype "passive"))
    )
    (net (code "24") (name "CF2") (class "Default")
      (node (ref "CONFIG") (pin "4") (pinfunction "4_4") (pintype "passive"))
      (node (ref "CONFIGSW") (pin "5") (pinfunction "5_5") (pintype "passive"))
      (node (ref "IC18") (pin "14") (pinfunction "D_14") (pintype "input"))
      (node (ref "R6") (pin "2") (pinfunction "2_2") (pintype "passive"))
    )
    (net (code "25") (name "CF3") (class "Default")
      (node (ref "CONFIG") (pin "6") (pinfunction "6_6") (pintype "passive"))
      (node (ref "CONFIGSW") (pin "4") (pinfunction "4_4") (pintype "passive"))
      (node (ref "IC18") (pin "3") (pinfunction "E_3") (pintype "input"))
      (node (ref "R7") (pin "2") (pinfunction "2_2") (pintype "passive"))
    )
    (net (code "26") (name "CF4") (class "Default")
      (node (ref "CONFIG") (pin "8") (pinfunction "8_8") (pintype "passive"))
      (node (ref "CONFIGSW") (pin "3") (pinfunction "3_3") (pintype "passive"))
      (node (ref "IC18") (pin "4") (pinfunction "F_4") (pintype "input"))
      (node (ref "R8") (pin "2") (pinfunction "2_2") (pintype "passive"))
    )
    (net (code "27") (name "CF5") (class "Default")
      (node (ref "CONFIG") (pin "10") (pinfunction "10_10") (pintype "passive"))
      (node (ref "CONFIGSW") (pin "2") (pinfunction "2_2") (pintype "passive"))
      (node (ref "IC18") (pin "5") (pinfunction "G_5") (pintype "input"))
      (node (ref "R9") (pin "2") (pinfunction "2_2") (pintype "passive"))
    )
    (net (code "28") (name "CF6") (class "Default")
      (node (ref "CONFIG") (pin "12") (pinfunction "12_12") (pintype "passive"))
      (node (ref "CONFIGSW") (pin "1") (pinfunction "1_1") (pintype "passive"))
      (node (ref "IC18") (pin "6") (pinfunction "H_6") (pintype "input"))
      (node (ref "R10") (pin "2") (pinfunction "2_2") (pintype "passive"))
    )
    (net (code "29") (name "CLK") (class "Default")
      (node (ref "SLOT2") (pin "21") (pinfunction "21_21") (pintype "passive"))
      (node (ref "XESS") (pin "13") (pinfunction "F14_13") (pintype "bidirectional"))
    )
    (net (code "30") (name "CONT") (class "Default")
      (node (ref "B40") (pin "28") (pinfunction "28_28") (pintype "passive"))
      (node (ref "IC2") (pin "5") (pinfunction "G_5") (pintype "input"))
      (node (ref "R46") (pin "1") (pinfunction "1_1") (pintype "passive"))
    )
    (net (code "31") (name "DCA") (class "Default")
      (node (ref "D40") (pin "8") (pinfunction "8_8") (pintype "passive"))
      (node (ref "R51") (pin "2") (pinfunction "2_2") (pintype "passive"))
    )
    (net (code "32") (name "DEFER") (class "Default")
      (node (ref "D40") (pin "26") (pinfunction "26_26") (pintype "passive"))
      (node (ref "R66") (pin "2") (pinfunction "2_2") (pintype "passive"))
    )
    (net (code "33") (name "DEP") (class "Default")
      (node (ref "B40") (pin "20") (pinfunction "20_20") (pintype "passive"))
      (node (ref "IC2") (pin "3") (pinfunction "E_3") (pintype "input"))
      (node (ref "R44") (pin "1") (pinfunction "1_1") (pintype "passive"))
    )
    (net (code "34") (name "DF0") (class "Default")
      (node (ref "C40") (pin "1") (pinfunction "1_1") (pintype "passive"))
      (node (ref "R128") (pin "2") (pinfunction "2_2") (pintype "passive"))
    )
    (net (code "35") (name "DF1") (class "Default")
      (node (ref "C40") (pin "10") (pinfunction "10_10") (pintype "passive"))
      (node (ref "R130") (pin "2") (pinfunction "2_2") (pintype "passive"))
    )
    (net (code "36") (name "DF2") (class "Default")
      (node (ref "C40") (pin "11") (pinfunction "11_11") (pintype "passive"))
      (node (ref "R132") (pin "2") (pinfunction "2_2") (pintype "passive"))
    )
    (net (code "37") (name "EXAM") (class "Default")
      (node (ref "B40") (pin "26") (pinfunction "26_26") (pintype "passive"))
      (node (ref "IC2") (pin "4") (pinfunction "F_4") (pintype "input"))
      (node (ref "R45") (pin "1") (pinfunction "1_1") (pintype "passive"))
    )
    (net (code "38") (name "EXECUTE") (class "Default")
      (node (ref "D40") (pin "28") (pinfunction "28_28") (pintype "passive"))
      (node (ref "R65") (pin "2") (pinfunction "2_2") (pintype "passive"))
    )
    (net (code "39") (name "FETCH") (class "Default")
      (node (ref "D40") (pin "24") (pinfunction "24_24") (pintype "passive"))
      (node (ref "R56") (pin "2") (pinfunction "2_2") (pintype "passive"))
    )
    (net (code "40") (name "GND") (class "Default")
      (node (ref "A40") (pin "4") (pinfunction "4_4") (pintype "passive"))
      (node (ref "B40") (pin "4") (pinfunction "4_4") (pintype "passive"))
      (node (ref "C10") (pin "2") (pinfunction "2_2") (pintype "passive"))
      (node (ref "C11") (pin "2") (pinfunction "2_2") (pintype "passive"))
      (node (ref "C12") (pin "2") (pinfunction "2_2") (pintype "passive"))
      (node (ref "C13") (pin "2") (pinfunction "2_2") (pintype "passive"))
      (node (ref "C14") (pin "2") (pinfunction "2_2") (pintype "passive"))
      (node (ref "C15") (pin "2") (pinfunction "2_2") (pintype "passive"))
      (node (ref "C16") (pin "2") (pinfunction "2_2") (pintype "passive"))
      (node (ref "C17") (pin "2") (pinfunction "2_2") (pintype "passive"))
      (node (ref "C18") (pin "2") (pinfunction "2_2") (pintype "passive"))
      (node (ref "C19") (pin "2") (pinfunction "2_2") (pintype "passive"))
      (node (ref "C20") (pin "2") (pinfunction "2_2") (pintype "passive"))
      (node (ref "C21") (pin "2") (pinfunction "2_2") (pintype "passive"))
      (node (ref "C22") (pin "2") (pinfunction "2_2") (pintype "passive"))
      (node (ref "C23") (pin "2") (pinfunction "2_2") (pintype "passive"))
      (node (ref "C24") (pin "2") (pinfunction "2_2") (pintype "passive"))
      (node (ref "C25") (pin "2") (pinfunction "2_2") (pintype "passive"))
      (node (ref "C4") (pin "2") (pinfunction "2_2") (pintype "passive"))
      (node (ref "C40") (pin "17") (pinfunction "17_17") (pintype "passive"))
      (node (ref "C40") (pin "18") (pinfunction "18_18") (pintype "passive"))
      (node (ref "C40") (pin "19") (pinfunction "19_19") (pintype "passive"))
      (node (ref "C40") (pin "20") (pinfunction "20_20") (pintype "passive"))
      (node (ref "C5") (pin "2") (pinfunction "2_2") (pintype "passive"))
      (node (ref "C6") (pin "2") (pinfunction "2_2") (pintype "passive"))
      (node (ref "C7") (pin "2") (pinfunction "2_2") (pintype "passive"))
      (node (ref "C8") (pin "2") (pinfunction "2_2") (pintype "passive"))
      (node (ref "C9") (pin "2") (pinfunction "2_2") (pintype "passive"))
      (node (ref "CONFIG") (pin "1") (pinfunction "1_1") (pintype "passive"))
      (node (ref "CONFIG") (pin "11") (pinfunction "11_11") (pintype "passive"))
      (node (ref "CONFIG") (pin "3") (pinfunction "3_3") (pintype "passive"))
      (node (ref "CONFIG") (pin "5") (pinfunction "5_5") (pintype "passive"))
      (node (ref "CONFIG") (pin "7") (pinfunction "7_7") (pintype "passive"))
      (node (ref "CONFIG") (pin "9") (pinfunction "9_9") (pintype "passive"))
      (node (ref "CONFIGSW") (pin "10") (pinfunction "10_10") (pintype "passive"))
      (node (ref "CONFIGSW") (pin "11") (pinfunction "11_11") (pintype "passive"))
      (node (ref "CONFIGSW") (pin "12") (pinfunction "12_12") (pintype "passive"))
      (node (ref "CONFIGSW") (pin "13") (pinfunction "13_13") (pintype "passive"))
      (node (ref "CONFIGSW") (pin "14") (pinfunction "14_14") (pintype "passive"))
      (node (ref "CONFIGSW") (pin "15") (pinfunction "15_15") (pintype "passive"))
      (node (ref "CONFIGSW") (pin "16") (pinfunction "16_16") (pintype "passive"))
      (node (ref "CONFIGSW") (pin "17") (pinfunction "17_17") (pintype "passive"))
      (node (ref "CONFIGSW") (pin "18") (pinfunction "18_18") (pintype "passive"))
      (node (ref "D1") (pin "A") (pinfunction "A_A") (pintype "passive"))
      (node (ref "D2") (pin "A") (pinfunction "A_A") (pintype "passive"))
      (node (ref "D40") (pin "17") (pinfunction "17_17") (pintype "passive"))
      (node (ref "D40") (pin "18") (pinfunction "18_18") (pintype "passive"))
      (node (ref "D40") (pin "19") (pinfunction "19_19") (pintype "passive"))
      (node (ref "D40") (pin "20") (pinfunction "20_20") (pintype "passive"))
      (node (ref "E40") (pin "17") (pinfunction "17_17") (pintype "passive"))
      (node (ref "E40") (pin "18") (pinfunction "18_18") (pintype "passive"))
      (node (ref "E40") (pin "19") (pinfunction "19_19") (pintype "passive"))
      (node (ref "E40") (pin "20") (pinfunction "20_20") (pintype "passive"))
      (node (ref "EXTRESET") (pin "3") (pinfunction "P_3") (pintype "passive"))
      (node (ref "EXTRESET") (pin "4") (pinfunction "P1_4") (pintype "passive"))
      (node (ref "F40") (pin "17") (pinfunction "17_17") (pintype "passive"))
      (node (ref "F40") (pin "18") (pinfunction "18_18") (pintype "passive"))
      (node (ref "F40") (pin "19") (pinfunction "19_19") (pintype "passive"))
      (node (ref "F40") (pin "20") (pinfunction "20_20") (pintype "passive"))
      (node (ref "GND1") (pin "1") (pinfunction "1_1") (pintype "passive"))
      (node (ref "GND2") (pin "1") (pinfunction "1_1") (pintype "passive"))
      (node (ref "GND3") (pin "1") (pinfunction "1_1") (pintype "passive"))
      (node (ref "GND4") (pin "1") (pinfunction "1_1") (pintype "passive"))
      (node (ref "IC1") (pin "1") (pinfunction "OC_1") (pintype "input"))
      (node (ref "IC10") (pin "1") (pinfunction "OC_1") (pintype "input"))
      (node (ref "IC11") (pin "1") (pinfunction "OC_1") (pintype "input"))
      (node (ref "IC12") (pin "1") (pinfunction "OC_1") (pintype "input"))
      (node (ref "IC14") (pin "10") (pinfunction "SER_10") (pintype "input"))
      (node (ref "IC14") (pin "15") (pinfunction "INH_15") (pintype "input"))
      (node (ref "IC15") (pin "15") (pinfunction "INH_15") (pintype "input"))
      (node (ref "IC17") (pin "1") (pinfunction "G_1") (pintype "input"))
      (node (ref "IC17") (pin "19") (pinfunction "G_19") (pintype "input"))
      (node (ref "IC18") (pin "15") (pinfunction "INH_15") (pintype "input"))
      (node (ref "IC2") (pin "15") (pinfunction "INH_15") (pintype "input"))
      (node (ref "IC20") (pin "1") (pinfunction "OC_1") (pintype "input"))
      (node (ref "IC21") (pin "1") (pinfunction "OC_1") (pintype "input"))
      (node (ref "IC4") (pin "1") (pinfunction "OC_1") (pintype "input"))
      (node (ref "IC5") (pin "1") (pinfunction "OC_1") (pintype "input"))
      (node (ref "IC6") (pin "1") (pinfunction "OC_1") (pintype "input"))
      (node (ref "IC7") (pin "1") (pinfunction "OC_1") (pintype "input"))
      (node (ref "IC8") (pin "1") (pinfunction "OC_1") (pintype "input"))
      (node (ref "IC9") (pin "1") (pinfunction "OC_1") (pintype "input"))
      (node (ref "IDE") (pin "19") (pinfunction "19_19") (pintype "passive"))
      (node (ref "IDE") (pin "2") (pinfunction "2_2") (pintype "passive"))
      (node (ref "IDE") (pin "22") (pinfunction "22_22") (pintype "passive"))
      (node (ref "IDE") (pin "24") (pinfunction "24_24") (pintype "passive"))
      (node (ref "IDE") (pin "26") (pinfunction "26_26") (pintype "passive"))
      (node (ref "IDE") (pin "28") (pinfunction "28_28") (pintype "passive"))
      (node (ref "IDE") (pin "30") (pinfunction "30_30") (pintype "passive"))
      (node (ref "IDE") (pin "40") (pinfunction "40_40") (pintype "passive"))
      (node (ref "J1") (pin "2") (pinfunction "2_2") (pintype "passive"))
      (node (ref "J1") (pin "3") (pinfunction "3_3") (pintype "passive"))
      (node (ref "J3") (pin "2") (pinfunction "2_2") (pintype "passive"))
      (node (ref "J4") (pin "11") (pinfunction "CMN_11") (pintype "input"))
      (node (ref "LOCKSW") (pin "1") (pinfunction "1_1") (pintype "passive"))
      (node (ref "R17") (pin "1") (pinfunction "1_1") (pintype "passive"))
      (node (ref "R18") (pin "1") (pinfunction "1_1") (pintype "passive"))
      (node (ref "RS-232") (pin "3") (pinfunction "3_3") (pintype "passive"))
      (node (ref "SLOT2") (pin "19") (pinfunction "19_19") (pintype "passive"))
      (node (ref "SLOT2") (pin "2") (pinfunction "2_2") (pintype "passive"))
      (node (ref "SLOT2") (pin "22") (pinfunction "22_22") (pintype "passive"))
      (node (ref "SLOT2") (pin "24") (pinfunction "24_24") (pintype "passive"))
      (node (ref "SLOT2") (pin "26") (pinfunction "26_26") (pintype "passive"))
      (node (ref "SLOT2") (pin "30") (pinfunction "30_30") (pintype "passive"))
      (node (ref "SLOT2") (pin "40") (pinfunction "40_40") (pintype "passive"))
      (node (ref "V-") (pin "1") (pinfunction "1_1") (pintype "passive"))
      (node (ref "X1") (pin "5") (pinfunction "F_5") (pintype "passive"))
      (node (ref "X1") (pin "G1") (pinfunction "G1_G1") (pintype "passive"))
      (node (ref "X1") (pin "G2") (pinfunction "G2_G2") (pintype "passive"))
      (node (ref "XESS") (pin "52") (pinfunction "GND_52") (pintype "power_in"))
    )
    (net (code "41") (name "I2C-SCL") (class "Default")
      (node (ref "SLOT2") (pin "27") (pinfunction "27_27") (pintype "passive"))
      (node (ref "XESS") (pin "23") (pinfunction "F5_23") (pintype "bidirectional"))
    )
    (net (code "42") (name "I2C-SDA") (class "Default")
      (node (ref "SLOT2") (pin "29") (pinfunction "29_29") (pintype "passive"))
      (node (ref "XESS") (pin "24") (pinfunction "D2_24") (pintype "bidirectional"))
    )
    (net (code "43") (name "IDE-CS0#") (class "Default")
      (node (ref "IDE") (pin "37") (pinfunction "37_37") (pintype "passive"))
      (node (ref "XESS") (pin "7") (pinfunction "G15_7") (pintype "bidirectional"))
    )
    (net (code "44") (name "IDE-CS1#") (class "Default")
      (node (ref "IDE") (pin "38") (pinfunction "38_38") (pintype "passive"))
      (node (ref "XESS") (pin "8") (pinfunction "G14_8") (pintype "bidirectional"))
    )
    (net (code "45") (name "IDE-DMACK#") (class "Default")
      (node (ref "IDE") (pin "29") (pinfunction "29_29") (pintype "passive"))
      (node (ref "XESS") (pin "43") (pinfunction "K1_43") (pintype "bidirectional"))
    )
    (net (code "46") (name "IDE-DMARQ") (class "Default")
      (node (ref "R12") (pin "1") (pinfunction "1_1") (pintype "passive"))
      (node (ref "R17") (pin "2") (pinfunction "2_2") (pintype "passive"))
      (node (ref "XESS") (pin "49") (pinfunction "L4_49") (pintype "bidirectional"))
    )
    (net (code "47") (name "IDE-IORDY") (class "Default")
      (node (ref "R15") (pin "1") (pinfunction "1_1") (pintype "passive"))
      (node (ref "R19") (pin "1") (pinfunction "1_1") (pintype "passive"))
      (node (ref "XESS") (pin "44") (pinfunction "L2_44") (pintype "bidirectional"))
    )
    (net (code "48") (name "IDE-IRQ") (class "Default")
      (node (ref "R16") (pin "1") (pinfunction "1_1") (pintype "passive"))
      (node (ref "R18") (pin "2") (pinfunction "2_2") (pintype "passive"))
      (node (ref "XESS") (pin "3") (pinfunction "H15_3") (pintype "bidirectional"))
    )
    (net (code "49") (name "IF0") (class "Default")
      (node (ref "C40") (pin "24") (pinfunction "24_24") (pintype "passive"))
      (node (ref "R134") (pin "2") (pinfunction "2_2") (pintype "passive"))
    )
    (net (code "50") (name "IF1") (class "Default")
      (node (ref "C40") (pin "25") (pinfunction "25_25") (pintype "passive"))
      (node (ref "R136") (pin "2") (pinfunction "2_2") (pintype "passive"))
    )
    (net (code "51") (name "IF2") (class "Default")
      (node (ref "C40") (pin "34") (pinfunction "34_34") (pintype "passive"))
      (node (ref "R138") (pin "2") (pinfunction "2_2") (pintype "passive"))
    )
    (net (code "52") (name "ION") (class "Default")
      (node (ref "D40") (pin "34") (pinfunction "34_34") (pintype "passive"))
      (node (ref "R62") (pin "2") (pinfunction "2_2") (pintype "passive"))
    )
    (net (code "53") (name "IOT") (class "Default")
      (node (ref "D40") (pin "23") (pinfunction "23_23") (pintype "passive"))
      (node (ref "R55") (pin "2") (pinfunction "2_2") (pintype "passive"))
    )
    (net (code "54") (name "ISZ") (class "Default")
      (node (ref "D40") (pin "6") (pinfunction "6_6") (pintype "passive"))
      (node (ref "R52") (pin "2") (pinfunction "2_2") (pintype "passive"))
    )
    (net (code "55") (name "JMP") (class "Default")
      (node (ref "D40") (pin "12") (pinfunction "12_12") (pintype "passive"))
      (node (ref "R59") (pin "2") (pinfunction "2_2") (pintype "passive"))
    )
    (net (code "56") (name "JMS") (class "Default")
      (node (ref "D40") (pin "10") (pinfunction "10_10") (pintype "passive"))
      (node (ref "R97") (pin "2") (pinfunction "2_2") (pintype "passive"))
    )
    (net (code "57") (name "L0#") (class "Default")
      (node (ref "IC13") (pin "15") (pinfunction "Y0_15") (pintype "output"))
      (node (ref "IC20") (pin "11") (pinfunction "CLK_11") (pintype "input"))
      (node (ref "IC21") (pin "11") (pinfunction "CLK_11") (pintype "input"))
    )
    (net (code "58") (name "L1#") (class "Default")
      (node (ref "IC1") (pin "11") (pinfunction "CLK_11") (pintype "input"))
      (node (ref "IC13") (pin "14") (pinfunction "Y1_14") (pintype "output"))
      (node (ref "IC4") (pin "11") (pinfunction "CLK_11") (pintype "input"))
    )
    (net (code "59") (name "L2#") (class "Default")
      (node (ref "IC13") (pin "13") (pinfunction "Y2_13") (pintype "output"))
      (node (ref "IC5") (pin "11") (pinfunction "CLK_11") (pintype "input"))
      (node (ref "IC6") (pin "11") (pinfunction "CLK_11") (pintype "input"))
    )
    (net (code "60") (name "L3#") (class "Default")
      (node (ref "IC13") (pin "12") (pinfunction "Y3_12") (pintype "output"))
      (node (ref "IC7") (pin "11") (pinfunction "CLK_11") (pintype "input"))
      (node (ref "IC8") (pin "11") (pinfunction "CLK_11") (pintype "input"))
    )
    (net (code "61") (name "L4#") (class "Default")
      (node (ref "IC10") (pin "11") (pinfunction "CLK_11") (pintype "input"))
      (node (ref "IC13") (pin "11") (pinfunction "Y4_11") (pintype "output"))
      (node (ref "IC9") (pin "11") (pinfunction "CLK_11") (pintype "input"))
    )
    (net (code "62") (name "L5#") (class "Default")
      (node (ref "IC11") (pin "11") (pinfunction "CLK_11") (pintype "input"))
      (node (ref "IC12") (pin "11") (pinfunction "CLK_11") (pintype "input"))
      (node (ref "IC13") (pin "10") (pinfunction "Y5_10") (pintype "output"))
    )
    (net (code "63") (name "LA") (class "Default")
      (node (ref "B40") (pin "18") (pinfunction "18_18") (pintype "passive"))
      (node (ref "IC2") (pin "14") (pinfunction "D_14") (pintype "input"))
      (node (ref "R43") (pin "1") (pinfunction "1_1") (pintype "passive"))
    )
    (net (code "64") (name "LCLK") (class "Default")
      (node (ref "IC17") (pin "14") (pinfunction "Y3_14") (pintype "tri_state"))
      (node (ref "IC17") (pin "16") (pinfunction "Y2_16") (pintype "tri_state"))
    )
    (net (code "65") (name "LINK") (class "Default")
      (node (ref "C40") (pin "28") (pinfunction "28_28") (pintype "passive"))
      (node (ref "R139") (pin "2") (pinfunction "2_2") (pintype "passive"))
    )
    (net (code "66") (name "LSER") (class "Default")
      (node (ref "IC17") (pin "18") (pinfunction "Y1_18") (pintype "tri_state"))
    )
    (net (code "67") (name "MA0") (class "Default")
      (node (ref "E40") (pin "3") (pinfunction "3_3") (pintype "passive"))
      (node (ref "R99") (pin "2") (pinfunction "2_2") (pintype "passive"))
    )
    (net (code "68") (name "MA1") (class "Default")
      (node (ref "E40") (pin "8") (pinfunction "8_8") (pintype "passive"))
      (node (ref "R104") (pin "2") (pinfunction "2_2") (pintype "passive"))
    )
    (net (code "69") (name "MA2") (class "Default")
      (node (ref "E40") (pin "13") (pinfunction "13_13") (pintype "passive"))
      (node (ref "R109") (pin "2") (pinfunction "2_2") (pintype "passive"))
    )
    (net (code "70") (name "MA3") (class "Default")
      (node (ref "E40") (pin "22") (pinfunction "22_22") (pintype "passive"))
      (node (ref "R114") (pin "2") (pinfunction "2_2") (pintype "passive"))
    )
    (net (code "71") (name "MA4") (class "Default")
      (node (ref "E40") (pin "27") (pinfunction "27_27") (pintype "passive"))
      (node (ref "R119") (pin "2") (pinfunction "2_2") (pintype "passive"))
    )
    (net (code "72") (name "MA5") (class "Default")
      (node (ref "E40") (pin "32") (pinfunction "32_32") (pintype "passive"))
      (node (ref "R124") (pin "2") (pinfunction "2_2") (pintype "passive"))
    )
    (net (code "73") (name "MA6") (class "Default")
      (node (ref "F40") (pin "3") (pinfunction "3_3") (pintype "passive"))
      (node (ref "R68") (pin "2") (pinfunction "2_2") (pintype "passive"))
    )
    (net (code "74") (name "MA7") (class "Default")
      (node (ref "F40") (pin "8") (pinfunction "8_8") (pintype "passive"))
      (node (ref "R73") (pin "2") (pinfunction "2_2") (pintype "passive"))
    )
    (net (code "75") (name "MA8") (class "Default")
      (node (ref "F40") (pin "13") (pinfunction "13_13") (pintype "passive"))
      (node (ref "R78") (pin "2") (pinfunction "2_2") (pintype "passive"))
    )
    (net (code "76") (name "MA9") (class "Default")
      (node (ref "F40") (pin "22") (pinfunction "22_22") (pintype "passive"))
      (node (ref "R83") (pin "2") (pinfunction "2_2") (pintype "passive"))
    )
    (net (code "77") (name "MA10") (class "Default")
      (node (ref "F40") (pin "27") (pinfunction "27_27") (pintype "passive"))
      (node (ref "R88") (pin "2") (pinfunction "2_2") (pintype "passive"))
    )
    (net (code "78") (name "MA11") (class "Default")
      (node (ref "F40") (pin "32") (pinfunction "32_32") (pintype "passive"))
      (node (ref "R93") (pin "2") (pinfunction "2_2") (pintype "passive"))
    )
    (net (code "79") (name "MASTER-RESET#") (class "Default")
      (node (ref "IC17") (pin "3") (pinfunction "Y4_3") (pintype "tri_state"))
      (node (ref "IDE") (pin "1") (pinfunction "1_1") (pintype "passive"))
      (node (ref "SLOT2") (pin "1") (pinfunction "1_1") (pintype "passive"))
    )
    (net (code "80") (name "MB0") (class "Default")
      (node (ref "E40") (pin "5") (pinfunction "5_5") (pintype "passive"))
      (node (ref "R100") (pin "2") (pinfunction "2_2") (pintype "passive"))
    )
    (net (code "81") (name "MB1") (class "Default")
      (node (ref "E40") (pin "6") (pinfunction "6_6") (pintype "passive"))
      (node (ref "R105") (pin "2") (pinfunction "2_2") (pintype "passive"))
    )
    (net (code "82") (name "MB2") (class "Default")
      (node (ref "E40") (pin "15") (pinfunction "15_15") (pintype "passive"))
      (node (ref "R110") (pin "2") (pinfunction "2_2") (pintype "passive"))
    )
    (net (code "83") (name "MB3") (class "Default")
      (node (ref "E40") (pin "16") (pinfunction "16_16") (pintype "passive"))
      (node (ref "R115") (pin "2") (pinfunction "2_2") (pintype "passive"))
    )
    (net (code "84") (name "MB4") (class "Default")
      (node (ref "E40") (pin "29") (pinfunction "29_29") (pintype "passive"))
      (node (ref "R120") (pin "2") (pinfunction "2_2") (pintype "passive"))
    )
    (net (code "85") (name "MB5") (class "Default")
      (node (ref "E40") (pin "30") (pinfunction "30_30") (pintype "passive"))
      (node (ref "R125") (pin "2") (pinfunction "2_2") (pintype "passive"))
    )
    (net (code "86") (name "MB6") (class "Default")
      (node (ref "F40") (pin "5") (pinfunction "5_5") (pintype "passive"))
      (node (ref "R69") (pin "2") (pinfunction "2_2") (pintype "passive"))
    )
    (net (code "87") (name "MB7") (class "Default")
      (node (ref "F40") (pin "6") (pinfunction "6_6") (pintype "passive"))
      (node (ref "R74") (pin "2") (pinfunction "2_2") (pintype "passive"))
    )
    (net (code "88") (name "MB8") (class "Default")
      (node (ref "F40") (pin "15") (pinfunction "15_15") (pintype "passive"))
      (node (ref "R79") (pin "2") (pinfunction "2_2") (pintype "passive"))
    )
    (net (code "89") (name "MB9") (class "Default")
      (node (ref "F40") (pin "16") (pinfunction "16_16") (pintype "passive"))
      (node (ref "R84") (pin "2") (pinfunction "2_2") (pintype "passive"))
    )
    (net (code "90") (name "MB10") (class "Default")
      (node (ref "F40") (pin "29") (pinfunction "29_29") (pintype "passive"))
      (node (ref "R89") (pin "2") (pinfunction "2_2") (pintype "passive"))
    )
    (net (code "91") (name "MB11") (class "Default")
      (node (ref "F40") (pin "30") (pinfunction "30_30") (pintype "passive"))
      (node (ref "R94") (pin "2") (pinfunction "2_2") (pintype "passive"))
    )
    (net (code "92") (name "MQ0") (class "Default")
      (node (ref "E40") (pin "9") (pinfunction "9_9") (pintype "passive"))
      (node (ref "R102") (pin "2") (pinfunction "2_2") (pintype "passive"))
    )
    (net (code "93") (name "MQ1") (class "Default")
      (node (ref "E40") (pin "2") (pinfunction "2_2") (pintype "passive"))
      (node (ref "R107") (pin "2") (pinfunction "2_2") (pintype "passive"))
    )
    (net (code "94") (name "MQ2") (class "Default")
      (node (ref "E40") (pin "23") (pinfunction "23_23") (pintype "passive"))
      (node (ref "R112") (pin "2") (pinfunction "2_2") (pintype "passive"))
    )
    (net (code "95") (name "MQ3") (class "Default")
      (node (ref "E40") (pin "12") (pinfunction "12_12") (pintype "passive"))
      (node (ref "R117") (pin "2") (pinfunction "2_2") (pintype "passive"))
    )
    (net (code "96") (name "MQ4") (class "Default")
      (node (ref "E40") (pin "33") (pinfunction "33_33") (pintype "passive"))
      (node (ref "R122") (pin "2") (pinfunction "2_2") (pintype "passive"))
    )
    (net (code "97") (name "MQ5") (class "Default")
      (node (ref "E40") (pin "26") (pinfunction "26_26") (pintype "passive"))
      (node (ref "R127") (pin "2") (pinfunction "2_2") (pintype "passive"))
    )
    (net (code "98") (name "MQ6") (class "Default")
      (node (ref "F40") (pin "9") (pinfunction "9_9") (pintype "passive"))
      (node (ref "R71") (pin "2") (pinfunction "2_2") (pintype "passive"))
    )
    (net (code "99") (name "MQ7") (class "Default")
      (node (ref "F40") (pin "2") (pinfunction "2_2") (pintype "passive"))
      (node (ref "R76") (pin "2") (pinfunction "2_2") (pintype "passive"))
    )
    (net (code "100") (name "MQ8") (class "Default")
      (node (ref "F40") (pin "23") (pinfunction "23_23") (pintype "passive"))
      (node (ref "R81") (pin "2") (pinfunction "2_2") (pintype "passive"))
    )
    (net (code "101") (name "MQ9") (class "Default")
      (node (ref "F40") (pin "12") (pinfunction "12_12") (pintype "passive"))
      (node (ref "R86") (pin "2") (pinfunction "2_2") (pintype "passive"))
    )
    (net (code "102") (name "MQ10") (class "Default")
      (node (ref "F40") (pin "33") (pinfunction "33_33") (pintype "passive"))
      (node (ref "R91") (pin "2") (pinfunction "2_2") (pintype "passive"))
    )
    (net (code "103") (name "MQ11") (class "Default")
      (node (ref "F40") (pin "26") (pinfunction "26_26") (pintype "passive"))
      (node (ref "R96") (pin "2") (pinfunction "2_2") (pintype "passive"))
    )
    (net (code "104") (name "Net-(+12V-Pad1)") (class "Default")
      (node (ref "+12V") (pin "1") (pinfunction "1_1") (pintype "passive"))
      (node (ref "J1") (pin "1") (pinfunction "1_1") (pintype "passive"))
    )
    (net (code "105") (name "Net-(EXTRESET-S)") (class "Default")
      (node (ref "C5") (pin "1") (pinfunction "1_1") (pintype "passive"))
      (node (ref "EXTRESET") (pin "1") (pinfunction "S_1") (pintype "passive"))
      (node (ref "EXTRESET") (pin "2") (pinfunction "S1_2") (pintype "passive"))
      (node (ref "IC17") (pin "17") (pinfunction "A4_17") (pintype "input"))
      (node (ref "R20") (pin "2") (pinfunction "2_2") (pintype "passive"))
      (node (ref "R23") (pin "2") (pinfunction "2_2") (pintype "passive"))
    )
    (net (code "106") (name "Net-(IC1A-1Q)") (class "Default")
      (node (ref "IC1") (pin "2") (pinfunction "1Q_2") (pintype "tri_state"))
      (node (ref "R98") (pin "1") (pinfunction "1_1") (pintype "passive"))
    )
    (net (code "107") (name "Net-(IC1A-2Q)") (class "Default")
      (node (ref "IC1") (pin "5") (pinfunction "2Q_5") (pintype "tri_state"))
      (node (ref "R99") (pin "1") (pinfunction "1_1") (pintype "passive"))
    )
    (net (code "108") (name "Net-(IC1A-3Q)") (class "Default")
      (node (ref "IC1") (pin "6") (pinfunction "3Q_6") (pintype "tri_state"))
      (node (ref "R100") (pin "1") (pinfunction "1_1") (pintype "passive"))
    )
    (net (code "109") (name "Net-(IC1A-4Q)") (class "Default")
      (node (ref "IC1") (pin "9") (pinfunction "4Q_9") (pintype "tri_state"))
      (node (ref "R101") (pin "1") (pinfunction "1_1") (pintype "passive"))
    )
    (net (code "110") (name "Net-(IC1A-5Q)") (class "Default")
      (node (ref "IC1") (pin "12") (pinfunction "5Q_12") (pintype "tri_state"))
      (node (ref "R102") (pin "1") (pinfunction "1_1") (pintype "passive"))
    )
    (net (code "111") (name "Net-(IC1A-6Q)") (class "Default")
      (node (ref "IC1") (pin "15") (pinfunction "6Q_15") (pintype "tri_state"))
      (node (ref "R103") (pin "1") (pinfunction "1_1") (pintype "passive"))
    )
    (net (code "112") (name "Net-(IC1A-7Q)") (class "Default")
      (node (ref "IC1") (pin "16") (pinfunction "7Q_16") (pintype "tri_state"))
      (node (ref "R104") (pin "1") (pinfunction "1_1") (pintype "passive"))
    )
    (net (code "113") (name "Net-(IC1A-8Q)") (class "Default")
      (node (ref "IC1") (pin "19") (pinfunction "8Q_19") (pintype "tri_state"))
      (node (ref "R105") (pin "1") (pinfunction "1_1") (pintype "passive"))
    )
    (net (code "114") (name "Net-(IC3A-C1+)") (class "Default")
      (node (ref "C2") (pin "1") (pinfunction "1_1") (pintype "passive"))
      (node (ref "IC3") (pin "1") (pinfunction "C1+_1") (pintype "bidirectional"))
    )
    (net (code "115") (name "Net-(IC3A-C1-)") (class "Default")
      (node (ref "C2") (pin "2") (pinfunction "2_2") (pintype "passive"))
      (node (ref "IC3") (pin "3") (pinfunction "C1-_3") (pintype "bidirectional"))
    )
    (net (code "116") (name "Net-(IC3A-C2+)") (class "Default")
      (node (ref "C3") (pin "1") (pinfunction "1_1") (pintype "passive"))
      (node (ref "IC3") (pin "4") (pinfunction "C2+_4") (pintype "bidirectional"))
    )
    (net (code "117") (name "Net-(IC3A-C2-)") (class "Default")
      (node (ref "C3") (pin "2") (pinfunction "2_2") (pintype "passive"))
      (node (ref "IC3") (pin "5") (pinfunction "C2-_5") (pintype "bidirectional"))
    )
    (net (code "118") (name "Net-(IC3A-R2OUT)") (class "Default")
      (node (ref "IC3") (pin "9") (pinfunction "R2OUT_9") (pintype "output"))
      (node (ref "R2") (pin "2") (pinfunction "2_2") (pintype "passive"))
    )
    (net (code "119") (name "Net-(IC3A-T1IN)") (class "Default")
      (node (ref "IC3") (pin "11") (pinfunction "T1IN_11") (pintype "input"))
      (node (ref "R1") (pin "2") (pinfunction "2_2") (pintype "passive"))
    )
    (net (code "120") (name "Net-(IC3A-T2IN)") (class "Default")
      (node (ref "IC3") (pin "10") (pinfunction "T2IN_10") (pintype "input"))
      (node (ref "R3") (pin "2") (pinfunction "2_2") (pintype "passive"))
    )
    (net (code "121") (name "Net-(IC3A-V+)") (class "Default")
      (node (ref "C1") (pin "2") (pinfunction "2_2") (pintype "passive"))
      (node (ref "IC3") (pin "2") (pinfunction "V+_2") (pintype "bidirectional"))
    )
    (net (code "122") (name "Net-(IC3A-V-)") (class "Default")
      (node (ref "C4") (pin "1") (pinfunction "1_1") (pintype "passive"))
      (node (ref "IC3") (pin "6") (pinfunction "V-_6") (pintype "bidirectional"))
    )
    (net (code "123") (name "Net-(IC4A-1Q)") (class "Default")
      (node (ref "IC4") (pin "2") (pinfunction "1Q_2") (pintype "tri_state"))
      (node (ref "R106") (pin "1") (pinfunction "1_1") (pintype "passive"))
    )
    (net (code "124") (name "Net-(IC4A-2Q)") (class "Default")
      (node (ref "IC4") (pin "5") (pinfunction "2Q_5") (pintype "tri_state"))
      (node (ref "R107") (pin "1") (pinfunction "1_1") (pintype "passive"))
    )
    (net (code "125") (name "Net-(IC4A-3Q)") (class "Default")
      (node (ref "IC4") (pin "6") (pinfunction "3Q_6") (pintype "tri_state"))
      (node (ref "R108") (pin "1") (pinfunction "1_1") (pintype "passive"))
    )
    (net (code "126") (name "Net-(IC4A-4Q)") (class "Default")
      (node (ref "IC4") (pin "9") (pinfunction "4Q_9") (pintype "tri_state"))
      (node (ref "R109") (pin "1") (pinfunction "1_1") (pintype "passive"))
    )
    (net (code "127") (name "Net-(IC4A-5Q)") (class "Default")
      (node (ref "IC4") (pin "12") (pinfunction "5Q_12") (pintype "tri_state"))
      (node (ref "R110") (pin "1") (pinfunction "1_1") (pintype "passive"))
    )
    (net (code "128") (name "Net-(IC4A-6Q)") (class "Default")
      (node (ref "IC4") (pin "15") (pinfunction "6Q_15") (pintype "tri_state"))
      (node (ref "R111") (pin "1") (pinfunction "1_1") (pintype "passive"))
    )
    (net (code "129") (name "Net-(IC4A-7Q)") (class "Default")
      (node (ref "IC4") (pin "16") (pinfunction "7Q_16") (pintype "tri_state"))
      (node (ref "R112") (pin "1") (pinfunction "1_1") (pintype "passive"))
    )
    (net (code "130") (name "Net-(IC4A-8Q)") (class "Default")
      (node (ref "IC4") (pin "19") (pinfunction "8Q_19") (pintype "tri_state"))
      (node (ref "R113") (pin "1") (pinfunction "1_1") (pintype "passive"))
    )
    (net (code "131") (name "Net-(IC5A-1Q)") (class "Default")
      (node (ref "IC5") (pin "2") (pinfunction "1Q_2") (pintype "tri_state"))
      (node (ref "R114") (pin "1") (pinfunction "1_1") (pintype "passive"))
    )
    (net (code "132") (name "Net-(IC5A-2Q)") (class "Default")
      (node (ref "IC5") (pin "5") (pinfunction "2Q_5") (pintype "tri_state"))
      (node (ref "R115") (pin "1") (pinfunction "1_1") (pintype "passive"))
    )
    (net (code "133") (name "Net-(IC5A-3Q)") (class "Default")
      (node (ref "IC5") (pin "6") (pinfunction "3Q_6") (pintype "tri_state"))
      (node (ref "R116") (pin "1") (pinfunction "1_1") (pintype "passive"))
    )
    (net (code "134") (name "Net-(IC5A-4Q)") (class "Default")
      (node (ref "IC5") (pin "9") (pinfunction "4Q_9") (pintype "tri_state"))
      (node (ref "R117") (pin "1") (pinfunction "1_1") (pintype "passive"))
    )
    (net (code "135") (name "Net-(IC5A-5Q)") (class "Default")
      (node (ref "IC5") (pin "12") (pinfunction "5Q_12") (pintype "tri_state"))
      (node (ref "R118") (pin "1") (pinfunction "1_1") (pintype "passive"))
    )
    (net (code "136") (name "Net-(IC5A-6Q)") (class "Default")
      (node (ref "IC5") (pin "15") (pinfunction "6Q_15") (pintype "tri_state"))
      (node (ref "R119") (pin "1") (pinfunction "1_1") (pintype "passive"))
    )
    (net (code "137") (name "Net-(IC5A-7Q)") (class "Default")
      (node (ref "IC5") (pin "16") (pinfunction "7Q_16") (pintype "tri_state"))
      (node (ref "R120") (pin "1") (pinfunction "1_1") (pintype "passive"))
    )
    (net (code "138") (name "Net-(IC5A-8Q)") (class "Default")
      (node (ref "IC5") (pin "19") (pinfunction "8Q_19") (pintype "tri_state"))
      (node (ref "R121") (pin "1") (pinfunction "1_1") (pintype "passive"))
    )
    (net (code "139") (name "Net-(IC6A-1Q)") (class "Default")
      (node (ref "IC6") (pin "2") (pinfunction "1Q_2") (pintype "tri_state"))
      (node (ref "R122") (pin "1") (pinfunction "1_1") (pintype "passive"))
    )
    (net (code "140") (name "Net-(IC6A-2Q)") (class "Default")
      (node (ref "IC6") (pin "5") (pinfunction "2Q_5") (pintype "tri_state"))
      (node (ref "R123") (pin "1") (pinfunction "1_1") (pintype "passive"))
    )
    (net (code "141") (name "Net-(IC6A-3Q)") (class "Default")
      (node (ref "IC6") (pin "6") (pinfunction "3Q_6") (pintype "tri_state"))
      (node (ref "R124") (pin "1") (pinfunction "1_1") (pintype "passive"))
    )
    (net (code "142") (name "Net-(IC6A-4Q)") (class "Default")
      (node (ref "IC6") (pin "9") (pinfunction "4Q_9") (pintype "tri_state"))
      (node (ref "R125") (pin "1") (pinfunction "1_1") (pintype "passive"))
    )
    (net (code "143") (name "Net-(IC6A-5Q)") (class "Default")
      (node (ref "IC6") (pin "12") (pinfunction "5Q_12") (pintype "tri_state"))
      (node (ref "R126") (pin "1") (pinfunction "1_1") (pintype "passive"))
    )
    (net (code "144") (name "Net-(IC6A-6Q)") (class "Default")
      (node (ref "IC6") (pin "15") (pinfunction "6Q_15") (pintype "tri_state"))
      (node (ref "R127") (pin "1") (pinfunction "1_1") (pintype "passive"))
    )
    (net (code "145") (name "Net-(IC7A-1Q)") (class "Default")
      (node (ref "IC7") (pin "2") (pinfunction "1Q_2") (pintype "tri_state"))
      (node (ref "R67") (pin "1") (pinfunction "1_1") (pintype "passive"))
    )
    (net (code "146") (name "Net-(IC7A-2Q)") (class "Default")
      (node (ref "IC7") (pin "5") (pinfunction "2Q_5") (pintype "tri_state"))
      (node (ref "R68") (pin "1") (pinfunction "1_1") (pintype "passive"))
    )
    (net (code "147") (name "Net-(IC7A-3Q)") (class "Default")
      (node (ref "IC7") (pin "6") (pinfunction "3Q_6") (pintype "tri_state"))
      (node (ref "R69") (pin "1") (pinfunction "1_1") (pintype "passive"))
    )
    (net (code "148") (name "Net-(IC7A-4Q)") (class "Default")
      (node (ref "IC7") (pin "9") (pinfunction "4Q_9") (pintype "tri_state"))
      (node (ref "R70") (pin "1") (pinfunction "1_1") (pintype "passive"))
    )
    (net (code "149") (name "Net-(IC7A-5Q)") (class "Default")
      (node (ref "IC7") (pin "12") (pinfunction "5Q_12") (pintype "tri_state"))
      (node (ref "R71") (pin "1") (pinfunction "1_1") (pintype "passive"))
    )
    (net (code "150") (name "Net-(IC7A-6Q)") (class "Default")
      (node (ref "IC7") (pin "15") (pinfunction "6Q_15") (pintype "tri_state"))
      (node (ref "R72") (pin "1") (pinfunction "1_1") (pintype "passive"))
    )
    (net (code "151") (name "Net-(IC7A-7Q)") (class "Default")
      (node (ref "IC7") (pin "16") (pinfunction "7Q_16") (pintype "tri_state"))
      (node (ref "R73") (pin "1") (pinfunction "1_1") (pintype "passive"))
    )
    (net (code "152") (name "Net-(IC7A-8Q)") (class "Default")
      (node (ref "IC7") (pin "19") (pinfunction "8Q_19") (pintype "tri_state"))
      (node (ref "R74") (pin "1") (pinfunction "1_1") (pintype "passive"))
    )
    (net (code "153") (name "Net-(IC8A-1Q)") (class "Default")
      (node (ref "IC8") (pin "2") (pinfunction "1Q_2") (pintype "tri_state"))
      (node (ref "R75") (pin "1") (pinfunction "1_1") (pintype "passive"))
    )
    (net (code "154") (name "Net-(IC8A-2Q)") (class "Default")
      (node (ref "IC8") (pin "5") (pinfunction "2Q_5") (pintype "tri_state"))
      (node (ref "R76") (pin "1") (pinfunction "1_1") (pintype "passive"))
    )
    (net (code "155") (name "Net-(IC8A-3Q)") (class "Default")
      (node (ref "IC8") (pin "6") (pinfunction "3Q_6") (pintype "tri_state"))
      (node (ref "R77") (pin "1") (pinfunction "1_1") (pintype "passive"))
    )
    (net (code "156") (name "Net-(IC8A-4Q)") (class "Default")
      (node (ref "IC8") (pin "9") (pinfunction "4Q_9") (pintype "tri_state"))
      (node (ref "R78") (pin "1") (pinfunction "1_1") (pintype "passive"))
    )
    (net (code "157") (name "Net-(IC8A-5Q)") (class "Default")
      (node (ref "IC8") (pin "12") (pinfunction "5Q_12") (pintype "tri_state"))
      (node (ref "R79") (pin "1") (pinfunction "1_1") (pintype "passive"))
    )
    (net (code "158") (name "Net-(IC8A-6Q)") (class "Default")
      (node (ref "IC8") (pin "15") (pinfunction "6Q_15") (pintype "tri_state"))
      (node (ref "R80") (pin "1") (pinfunction "1_1") (pintype "passive"))
    )
    (net (code "159") (name "Net-(IC8A-7Q)") (class "Default")
      (node (ref "IC8") (pin "16") (pinfunction "7Q_16") (pintype "tri_state"))
      (node (ref "R81") (pin "1") (pinfunction "1_1") (pintype "passive"))
    )
    (net (code "160") (name "Net-(IC8A-8Q)") (class "Default")
      (node (ref "IC8") (pin "19") (pinfunction "8Q_19") (pintype "tri_state"))
      (node (ref "R82") (pin "1") (pinfunction "1_1") (pintype "passive"))
    )
    (net (code "161") (name "Net-(IC9A-1Q)") (class "Default")
      (node (ref "IC9") (pin "2") (pinfunction "1Q_2") (pintype "tri_state"))
      (node (ref "R83") (pin "1") (pinfunction "1_1") (pintype "passive"))
    )
    (net (code "162") (name "Net-(IC9A-2Q)") (class "Default")
      (node (ref "IC9") (pin "5") (pinfunction "2Q_5") (pintype "tri_state"))
      (node (ref "R84") (pin "1") (pinfunction "1_1") (pintype "passive"))
    )
    (net (code "163") (name "Net-(IC9A-3Q)") (class "Default")
      (node (ref "IC9") (pin "6") (pinfunction "3Q_6") (pintype "tri_state"))
      (node (ref "R85") (pin "1") (pinfunction "1_1") (pintype "passive"))
    )
    (net (code "164") (name "Net-(IC9A-4Q)") (class "Default")
      (node (ref "IC9") (pin "9") (pinfunction "4Q_9") (pintype "tri_state"))
      (node (ref "R86") (pin "1") (pinfunction "1_1") (pintype "passive"))
    )
    (net (code "165") (name "Net-(IC9A-5Q)") (class "Default")
      (node (ref "IC9") (pin "12") (pinfunction "5Q_12") (pintype "tri_state"))
      (node (ref "R87") (pin "1") (pinfunction "1_1") (pintype "passive"))
    )
    (net (code "166") (name "Net-(IC9A-6Q)") (class "Default")
      (node (ref "IC9") (pin "15") (pinfunction "6Q_15") (pintype "tri_state"))
      (node (ref "R88") (pin "1") (pinfunction "1_1") (pintype "passive"))
    )
    (net (code "167") (name "Net-(IC9A-7Q)") (class "Default")
      (node (ref "IC9") (pin "16") (pinfunction "7Q_16") (pintype "tri_state"))
      (node (ref "R89") (pin "1") (pinfunction "1_1") (pintype "passive"))
    )
    (net (code "168") (name "Net-(IC9A-8Q)") (class "Default")
      (node (ref "IC9") (pin "19") (pinfunction "8Q_19") (pintype "tri_state"))
      (node (ref "R90") (pin "1") (pinfunction "1_1") (pintype "passive"))
    )
    (net (code "169") (name "Net-(IC10A-1Q)") (class "Default")
      (node (ref "IC10") (pin "2") (pinfunction "1Q_2") (pintype "tri_state"))
      (node (ref "R91") (pin "1") (pinfunction "1_1") (pintype "passive"))
    )
    (net (code "170") (name "Net-(IC10A-2Q)") (class "Default")
      (node (ref "IC10") (pin "5") (pinfunction "2Q_5") (pintype "tri_state"))
      (node (ref "R92") (pin "1") (pinfunction "1_1") (pintype "passive"))
    )
    (net (code "171") (name "Net-(IC10A-3Q)") (class "Default")
      (node (ref "IC10") (pin "6") (pinfunction "3Q_6") (pintype "tri_state"))
      (node (ref "R93") (pin "1") (pinfunction "1_1") (pintype "passive"))
    )
    (net (code "172") (name "Net-(IC10A-4Q)") (class "Default")
      (node (ref "IC10") (pin "9") (pinfunction "4Q_9") (pintype "tri_state"))
      (node (ref "R94") (pin "1") (pinfunction "1_1") (pintype "passive"))
    )
    (net (code "173") (name "Net-(IC10A-5Q)") (class "Default")
      (node (ref "IC10") (pin "12") (pinfunction "5Q_12") (pintype "tri_state"))
      (node (ref "R95") (pin "1") (pinfunction "1_1") (pintype "passive"))
    )
    (net (code "174") (name "Net-(IC10A-6Q)") (class "Default")
      (node (ref "IC10") (pin "15") (pinfunction "6Q_15") (pintype "tri_state"))
      (node (ref "R96") (pin "1") (pinfunction "1_1") (pintype "passive"))
    )
    (net (code "175") (name "Net-(IC10A-8Q)") (class "Default")
      (node (ref "IC10") (pin "19") (pinfunction "8Q_19") (pintype "tri_state"))
      (node (ref "R97") (pin "1") (pinfunction "1_1") (pintype "passive"))
    )
    (net (code "176") (name "Net-(IC11A-1Q)") (class "Default")
      (node (ref "IC11") (pin "2") (pinfunction "1Q_2") (pintype "tri_state"))
      (node (ref "R51") (pin "1") (pinfunction "1_1") (pintype "passive"))
    )
    (net (code "177") (name "Net-(IC11A-2Q)") (class "Default")
      (node (ref "IC11") (pin "5") (pinfunction "2Q_5") (pintype "tri_state"))
      (node (ref "R52") (pin "1") (pinfunction "1_1") (pintype "passive"))
    )
    (net (code "178") (name "Net-(IC11A-3Q)") (class "Default")
      (node (ref "IC11") (pin "6") (pinfunction "3Q_6") (pintype "tri_state"))
      (node (ref "R53") (pin "1") (pinfunction "1_1") (pintype "passive"))
    )
    (net (code "179") (name "Net-(IC11A-4Q)") (class "Default")
      (node (ref "IC11") (pin "9") (pinfunction "4Q_9") (pintype "tri_state"))
      (node (ref "R54") (pin "1") (pinfunction "1_1") (pintype "passive"))
    )
    (net (code "180") (name "Net-(IC11A-5Q)") (class "Default")
      (node (ref "IC11") (pin "12") (pinfunction "5Q_12") (pintype "tri_state"))
      (node (ref "R55") (pin "1") (pinfunction "1_1") (pintype "passive"))
    )
    (net (code "181") (name "Net-(IC11A-6Q)") (class "Default")
      (node (ref "IC11") (pin "15") (pinfunction "6Q_15") (pintype "tri_state"))
      (node (ref "R56") (pin "1") (pinfunction "1_1") (pintype "passive"))
    )
    (net (code "182") (name "Net-(IC11A-7Q)") (class "Default")
      (node (ref "IC11") (pin "16") (pinfunction "7Q_16") (pintype "tri_state"))
      (node (ref "R57") (pin "1") (pinfunction "1_1") (pintype "passive"))
    )
    (net (code "183") (name "Net-(IC11A-8Q)") (class "Default")
      (node (ref "IC11") (pin "19") (pinfunction "8Q_19") (pintype "tri_state"))
      (node (ref "R58") (pin "1") (pinfunction "1_1") (pintype "passive"))
    )
    (net (code "184") (name "Net-(IC12A-1Q)") (class "Default")
      (node (ref "IC12") (pin "2") (pinfunction "1Q_2") (pintype "tri_state"))
      (node (ref "R59") (pin "1") (pinfunction "1_1") (pintype "passive"))
    )
    (net (code "185") (name "Net-(IC12A-2Q)") (class "Default")
      (node (ref "IC12") (pin "5") (pinfunction "2Q_5") (pintype "tri_state"))
      (node (ref "R60") (pin "1") (pinfunction "1_1") (pintype "passive"))
    )
    (net (code "186") (name "Net-(IC12A-3Q)") (class "Default")
      (node (ref "IC12") (pin "6") (pinfunction "3Q_6") (pintype "tri_state"))
      (node (ref "R61") (pin "1") (pinfunction "1_1") (pintype "passive"))
    )
    (net (code "187") (name "Net-(IC12A-4Q)") (class "Default")
      (node (ref "IC12") (pin "9") (pinfunction "4Q_9") (pintype "tri_state"))
      (node (ref "R62") (pin "1") (pinfunction "1_1") (pintype "passive"))
    )
    (net (code "188") (name "Net-(IC12A-5Q)") (class "Default")
      (node (ref "IC12") (pin "12") (pinfunction "5Q_12") (pintype "tri_state"))
      (node (ref "R63") (pin "1") (pinfunction "1_1") (pintype "passive"))
    )
    (net (code "189") (name "Net-(IC12A-6Q)") (class "Default")
      (node (ref "IC12") (pin "15") (pinfunction "6Q_15") (pintype "tri_state"))
      (node (ref "R64") (pin "1") (pinfunction "1_1") (pintype "passive"))
    )
    (net (code "190") (name "Net-(IC12A-7Q)") (class "Default")
      (node (ref "IC12") (pin "16") (pinfunction "7Q_16") (pintype "tri_state"))
      (node (ref "R65") (pin "1") (pinfunction "1_1") (pintype "passive"))
    )
    (net (code "191") (name "Net-(IC12A-8Q)") (class "Default")
      (node (ref "IC12") (pin "19") (pinfunction "8Q_19") (pintype "tri_state"))
      (node (ref "R66") (pin "1") (pinfunction "1_1") (pintype "passive"))
    )
    (net (code "192") (name "Net-(IC14A-QH)") (class "Default")
      (node (ref "IC14") (pin "9") (pinfunction "QH_9") (pintype "output"))
      (node (ref "IC15") (pin "10") (pinfunction "SER_10") (pintype "input"))
    )
    (net (code "193") (name "Net-(IC15A-QH)") (class "Default")
      (node (ref "IC15") (pin "9") (pinfunction "QH_9") (pintype "output"))
      (node (ref "IC2") (pin "10") (pinfunction "SER_10") (pintype "input"))
    )
    (net (code "194") (name "Net-(IC17B-Y2)") (class "Default")
      (node (ref "IC17") (pin "7") (pinfunction "Y2_7") (pintype "tri_state"))
      (node (ref "R11") (pin "1") (pinfunction "1_1") (pintype "passive"))
    )
    (net (code "195") (name "Net-(IC18A-SER)") (class "Default")
      (node (ref "IC18") (pin "10") (pinfunction "SER_10") (pintype "input"))
      (node (ref "IC2") (pin "9") (pinfunction "QH_9") (pintype "output"))
    )
    (net (code "196") (name "Net-(IC20A-1Q)") (class "Default")
      (node (ref "IC20") (pin "2") (pinfunction "1Q_2") (pintype "tri_state"))
      (node (ref "R136") (pin "1") (pinfunction "1_1") (pintype "passive"))
    )
    (net (code "197") (name "Net-(IC20A-2Q)") (class "Default")
      (node (ref "IC20") (pin "5") (pinfunction "2Q_5") (pintype "tri_state"))
      (node (ref "R137") (pin "1") (pinfunction "1_1") (pintype "passive"))
    )
    (net (code "198") (name "Net-(IC20A-3Q)") (class "Default")
      (node (ref "IC20") (pin "6") (pinfunction "3Q_6") (pintype "tri_state"))
      (node (ref "R138") (pin "1") (pinfunction "1_1") (pintype "passive"))
    )
    (net (code "199") (name "Net-(IC20A-4Q)") (class "Default")
      (node (ref "IC20") (pin "9") (pinfunction "4Q_9") (pintype "tri_state"))
      (node (ref "R139") (pin "1") (pinfunction "1_1") (pintype "passive"))
    )
    (net (code "200") (name "Net-(IC21A-1Q)") (class "Default")
      (node (ref "IC21") (pin "2") (pinfunction "1Q_2") (pintype "tri_state"))
      (node (ref "R128") (pin "1") (pinfunction "1_1") (pintype "passive"))
    )
    (net (code "201") (name "Net-(IC21A-2Q)") (class "Default")
      (node (ref "IC21") (pin "5") (pinfunction "2Q_5") (pintype "tri_state"))
      (node (ref "R129") (pin "1") (pinfunction "1_1") (pintype "passive"))
    )
    (net (code "202") (name "Net-(IC21A-3Q)") (class "Default")
      (node (ref "IC21") (pin "6") (pinfunction "3Q_6") (pintype "tri_state"))
      (node (ref "R130") (pin "1") (pinfunction "1_1") (pintype "passive"))
    )
    (net (code "203") (name "Net-(IC21A-4Q)") (class "Default")
      (node (ref "IC21") (pin "9") (pinfunction "4Q_9") (pintype "tri_state"))
      (node (ref "R131") (pin "1") (pinfunction "1_1") (pintype "passive"))
    )
    (net (code "204") (name "Net-(IC21A-5Q)") (class "Default")
      (node (ref "IC21") (pin "12") (pinfunction "5Q_12") (pintype "tri_state"))
      (node (ref "R132") (pin "1") (pinfunction "1_1") (pintype "passive"))
    )
    (net (code "205") (name "Net-(IC21A-6Q)") (class "Default")
      (node (ref "IC21") (pin "15") (pinfunction "6Q_15") (pintype "tri_state"))
      (node (ref "R133") (pin "1") (pinfunction "1_1") (pintype "passive"))
    )
    (net (code "206") (name "Net-(IC21A-7Q)") (class "Default")
      (node (ref "IC21") (pin "16") (pinfunction "7Q_16") (pintype "tri_state"))
      (node (ref "R134") (pin "1") (pinfunction "1_1") (pintype "passive"))
    )
    (net (code "207") (name "Net-(IC21A-8Q)") (class "Default")
      (node (ref "IC21") (pin "19") (pinfunction "8Q_19") (pintype "tri_state"))
      (node (ref "R135") (pin "1") (pinfunction "1_1") (pintype "passive"))
    )
    (net (code "208") (name "Net-(IDE-Pad21)") (class "Default")
      (node (ref "IDE") (pin "21") (pinfunction "21_21") (pintype "passive"))
      (node (ref "R12") (pin "2") (pinfunction "2_2") (pintype "passive"))
    )
    (net (code "209") (name "Net-(IDE-Pad23)") (class "Default")
      (node (ref "IDE") (pin "23") (pinfunction "23_23") (pintype "passive"))
      (node (ref "R13") (pin "2") (pinfunction "2_2") (pintype "passive"))
    )
    (net (code "210") (name "Net-(IDE-Pad25)") (class "Default")
      (node (ref "IDE") (pin "25") (pinfunction "25_25") (pintype "passive"))
      (node (ref "R14") (pin "2") (pinfunction "2_2") (pintype "passive"))
    )
    (net (code "211") (name "Net-(IDE-Pad27)") (class "Default")
      (node (ref "IDE") (pin "27") (pinfunction "27_27") (pintype "passive"))
      (node (ref "R15") (pin "2") (pinfunction "2_2") (pintype "passive"))
    )
    (net (code "212") (name "Net-(IDE-Pad31)") (class "Default")
      (node (ref "IDE") (pin "31") (pinfunction "31_31") (pintype "passive"))
      (node (ref "R16") (pin "2") (pinfunction "2_2") (pintype "passive"))
    )
    (net (code "213") (name "Net-(R22-Pad2)") (class "Default")
      (node (ref "R22") (pin "2") (pinfunction "2_2") (pintype "passive"))
      (node (ref "SLOT2") (pin "31") (pinfunction "31_31") (pintype "passive"))
    )
    (net (code "214") (name "OPR") (class "Default")
      (node (ref "D40") (pin "16") (pinfunction "16_16") (pintype "passive"))
      (node (ref "R58") (pin "2") (pinfunction "2_2") (pintype "passive"))
    )
    (net (code "215") (name "PAUSE") (class "Default")
      (node (ref "D40") (pin "31") (pinfunction "31_31") (pintype "passive"))
      (node (ref "R60") (pin "2") (pinfunction "2_2") (pintype "passive"))
    )
    (net (code "216") (name "PB-A0") (class "Default")
      (node (ref "IC13") (pin "1") (pinfunction "A_1") (pintype "input"))
      (node (ref "IC13") (pin "2") (pinfunction "B_2") (pintype "input"))
      (node (ref "IDE") (pin "35") (pinfunction "35_35") (pintype "passive"))
      (node (ref "SLOT2") (pin "35") (pinfunction "35_35") (pintype "passive"))
      (node (ref "XESS") (pin "57") (pinfunction "L5_57") (pintype "bidirectional"))
    )
    (net (code "217") (name "PB-A1") (class "Default")
      (node (ref "IDE") (pin "33") (pinfunction "33_33") (pintype "passive"))
      (node (ref "SLOT2") (pin "33") (pinfunction "33_33") (pintype "passive"))
      (node (ref "XESS") (pin "56") (pinfunction "N2_56") (pintype "bidirectional"))
    )
    (net (code "218") (name "PB-A2") (class "Default")
      (node (ref "IC13") (pin "3") (pinfunction "C_3") (pintype "input"))
      (node (ref "IDE") (pin "36") (pinfunction "36_36") (pintype "passive"))
      (node (ref "SLOT2") (pin "36") (pinfunction "36_36") (pintype "passive"))
      (node (ref "XESS") (pin "51") (pinfunction "M3_51") (pintype "bidirectional"))
    )
    (net (code "219") (name "PB-A3") (class "Default")
      (node (ref "SLOT2") (pin "38") (pinfunction "38_38") (pintype "passive"))
      (node (ref "XESS") (pin "50") (pinfunction "N1_50") (pintype "bidirectional"))
    )
    (net (code "220") (name "PB-A4") (class "Default")
      (node (ref "SLOT2") (pin "39") (pinfunction "39_39") (pintype "passive"))
      (node (ref "XESS") (pin "70") (pinfunction "T13_70") (pintype "bidirectional"))
    )
    (net (code "221") (name "PB-D0") (class "Default")
      (node (ref "IC1") (pin "3") (pinfunction "1D_3") (pintype "input"))
      (node (ref "IC11") (pin "3") (pinfunction "1D_3") (pintype "input"))
      (node (ref "IC21") (pin "3") (pinfunction "1D_3") (pintype "input"))
      (node (ref "IC5") (pin "3") (pinfunction "1D_3") (pintype "input"))
      (node (ref "IC7") (pin "3") (pinfunction "1D_3") (pintype "input"))
      (node (ref "IC9") (pin "3") (pinfunction "1D_3") (pintype "input"))
      (node (ref "IDE") (pin "17") (pinfunction "17_17") (pintype "passive"))
      (node (ref "SLOT2") (pin "17") (pinfunction "17_17") (pintype "passive"))
      (node (ref "XESS") (pin "71") (pinfunction "P12_71") (pintype "bidirectional"))
    )
    (net (code "222") (name "PB-D1") (class "Default")
      (node (ref "IC1") (pin "4") (pinfunction "2D_4") (pintype "input"))
      (node (ref "IC11") (pin "4") (pinfunction "2D_4") (pintype "input"))
      (node (ref "IC21") (pin "4") (pinfunction "2D_4") (pintype "input"))
      (node (ref "IC5") (pin "4") (pinfunction "2D_4") (pintype "input"))
      (node (ref "IC7") (pin "4") (pinfunction "2D_4") (pintype "input"))
      (node (ref "IC9") (pin "4") (pinfunction "2D_4") (pintype "input"))
      (node (ref "IDE") (pin "15") (pinfunction "15_15") (pintype "passive"))
      (node (ref "SLOT2") (pin "15") (pinfunction "15_15") (pintype "passive"))
      (node (ref "XESS") (pin "40") (pinfunction "J1_40") (pintype "bidirectional"))
    )
    (net (code "223") (name "PB-D2") (class "Default")
      (node (ref "IC1") (pin "7") (pinfunction "3D_7") (pintype "input"))
      (node (ref "IC11") (pin "7") (pinfunction "3D_7") (pintype "input"))
      (node (ref "IC21") (pin "7") (pinfunction "3D_7") (pintype "input"))
      (node (ref "IC5") (pin "7") (pinfunction "3D_7") (pintype "input"))
      (node (ref "IC7") (pin "7") (pinfunction "3D_7") (pintype "input"))
      (node (ref "IC9") (pin "7") (pinfunction "3D_7") (pintype "input"))
      (node (ref "IDE") (pin "13") (pinfunction "13_13") (pintype "passive"))
      (node (ref "SLOT2") (pin "13") (pinfunction "13_13") (pintype "passive"))
      (node (ref "XESS") (pin "39") (pinfunction "H1_39") (pintype "bidirectional"))
    )
    (net (code "224") (name "PB-D3") (class "Default")
      (node (ref "IC1") (pin "8") (pinfunction "4D_8") (pintype "input"))
      (node (ref "IC11") (pin "8") (pinfunction "4D_8") (pintype "input"))
      (node (ref "IC21") (pin "8") (pinfunction "4D_8") (pintype "input"))
      (node (ref "IC5") (pin "8") (pinfunction "4D_8") (pintype "input"))
      (node (ref "IC7") (pin "8") (pinfunction "4D_8") (pintype "input"))
      (node (ref "IC9") (pin "8") (pinfunction "4D_8") (pintype "input"))
      (node (ref "IDE") (pin "11") (pinfunction "11_11") (pintype "passive"))
      (node (ref "SLOT2") (pin "11") (pinfunction "11_11") (pintype "passive"))
      (node (ref "XESS") (pin "38") (pinfunction "H3_38") (pintype "bidirectional"))
    )
    (net (code "225") (name "PB-D4") (class "Default")
      (node (ref "IC1") (pin "13") (pinfunction "5D_13") (pintype "input"))
      (node (ref "IC11") (pin "13") (pinfunction "5D_13") (pintype "input"))
      (node (ref "IC21") (pin "13") (pinfunction "5D_13") (pintype "input"))
      (node (ref "IC5") (pin "13") (pinfunction "5D_13") (pintype "input"))
      (node (ref "IC7") (pin "13") (pinfunction "5D_13") (pintype "input"))
      (node (ref "IC9") (pin "13") (pinfunction "5D_13") (pintype "input"))
      (node (ref "IDE") (pin "9") (pinfunction "9_9") (pintype "passive"))
      (node (ref "SLOT2") (pin "9") (pinfunction "9_9") (pintype "passive"))
      (node (ref "XESS") (pin "35") (pinfunction "G2_35") (pintype "bidirectional"))
    )
    (net (code "226") (name "PB-D5") (class "Default")
      (node (ref "IC1") (pin "14") (pinfunction "6D_14") (pintype "input"))
      (node (ref "IC11") (pin "14") (pinfunction "6D_14") (pintype "input"))
      (node (ref "IC21") (pin "14") (pinfunction "6D_14") (pintype "input"))
      (node (ref "IC5") (pin "14") (pinfunction "6D_14") (pintype "input"))
      (node (ref "IC7") (pin "14") (pinfunction "6D_14") (pintype "input"))
      (node (ref "IC9") (pin "14") (pinfunction "6D_14") (pintype "input"))
      (node (ref "IDE") (pin "7") (pinfunction "7_7") (pintype "passive"))
      (node (ref "SLOT2") (pin "7") (pinfunction "7_7") (pintype "passive"))
      (node (ref "XESS") (pin "80") (pinfunction "K15_80") (pintype "bidirectional"))
    )
    (net (code "227") (name "PB-D6") (class "Default")
      (node (ref "IC1") (pin "17") (pinfunction "7D_17") (pintype "input"))
      (node (ref "IC11") (pin "17") (pinfunction "7D_17") (pintype "input"))
      (node (ref "IC21") (pin "17") (pinfunction "7D_17") (pintype "input"))
      (node (ref "IC5") (pin "17") (pinfunction "7D_17") (pintype "input"))
      (node (ref "IC7") (pin "17") (pinfunction "7D_17") (pintype "input"))
      (node (ref "IC9") (pin "17") (pinfunction "7D_17") (pintype "input"))
      (node (ref "IDE") (pin "5") (pinfunction "5_5") (pintype "passive"))
      (node (ref "SLOT2") (pin "5") (pinfunction "5_5") (pintype "passive"))
      (node (ref "XESS") (pin "81") (pinfunction "K16_81") (pintype "bidirectional"))
    )
    (net (code "228") (name "PB-D7") (class "Default")
      (node (ref "IC1") (pin "18") (pinfunction "8D_18") (pintype "input"))
      (node (ref "IC11") (pin "18") (pinfunction "8D_18") (pintype "input"))
      (node (ref "IC21") (pin "18") (pinfunction "8D_18") (pintype "input"))
      (node (ref "IC5") (pin "18") (pinfunction "8D_18") (pintype "input"))
      (node (ref "IC7") (pin "18") (pinfunction "8D_18") (pintype "input"))
      (node (ref "IC9") (pin "18") (pinfunction "8D_18") (pintype "input"))
      (node (ref "IDE") (pin "3") (pinfunction "3_3") (pintype "passive"))
      (node (ref "SLOT2") (pin "3") (pinfunction "3_3") (pintype "passive"))
      (node (ref "XESS") (pin "10") (pinfunction "F15_10") (pintype "bidirectional"))
    )
    (net (code "229") (name "PB-D8") (class "Default")
      (node (ref "IC10") (pin "3") (pinfunction "1D_3") (pintype "input"))
      (node (ref "IC12") (pin "3") (pinfunction "1D_3") (pintype "input"))
      (node (ref "IC20") (pin "3") (pinfunction "1D_3") (pintype "input"))
      (node (ref "IC4") (pin "3") (pinfunction "1D_3") (pintype "input"))
      (node (ref "IC6") (pin "3") (pinfunction "1D_3") (pintype "input"))
      (node (ref "IC8") (pin "3") (pinfunction "1D_3") (pintype "input"))
      (node (ref "IDE") (pin "4") (pinfunction "4_4") (pintype "passive"))
      (node (ref "SLOT2") (pin "4") (pinfunction "4_4") (pintype "passive"))
      (node (ref "XESS") (pin "27") (pinfunction "E2_27") (pintype "bidirectional"))
    )
    (net (code "230") (name "PB-D9") (class "Default")
      (node (ref "IC10") (pin "4") (pinfunction "2D_4") (pintype "input"))
      (node (ref "IC12") (pin "4") (pinfunction "2D_4") (pintype "input"))
      (node (ref "IC20") (pin "4") (pinfunction "2D_4") (pintype "input"))
      (node (ref "IC4") (pin "4") (pinfunction "2D_4") (pintype "input"))
      (node (ref "IC6") (pin "4") (pinfunction "2D_4") (pintype "input"))
      (node (ref "IC8") (pin "4") (pinfunction "2D_4") (pintype "input"))
      (node (ref "IDE") (pin "6") (pinfunction "6_6") (pintype "passive"))
      (node (ref "SLOT2") (pin "6") (pinfunction "6_6") (pintype "passive"))
      (node (ref "XESS") (pin "28") (pinfunction "E1_28") (pintype "bidirectional"))
    )
    (net (code "231") (name "PB-D10") (class "Default")
      (node (ref "IC10") (pin "7") (pinfunction "3D_7") (pintype "input"))
      (node (ref "IC12") (pin "7") (pinfunction "3D_7") (pintype "input"))
      (node (ref "IC20") (pin "7") (pinfunction "3D_7") (pintype "input"))
      (node (ref "IC4") (pin "7") (pinfunction "3D_7") (pintype "input"))
      (node (ref "IC6") (pin "7") (pinfunction "3D_7") (pintype "input"))
      (node (ref "IC8") (pin "7") (pinfunction "3D_7") (pintype "input"))
      (node (ref "IDE") (pin "8") (pinfunction "8_8") (pintype "passive"))
      (node (ref "SLOT2") (pin "8") (pinfunction "8_8") (pintype "passive"))
      (node (ref "XESS") (pin "29") (pinfunction "F3_29") (pintype "bidirectional"))
    )
    (net (code "232") (name "PB-D11") (class "Default")
      (node (ref "IC10") (pin "8") (pinfunction "4D_8") (pintype "input"))
      (node (ref "IC12") (pin "8") (pinfunction "4D_8") (pintype "input"))
      (node (ref "IC20") (pin "8") (pinfunction "4D_8") (pintype "input"))
      (node (ref "IC4") (pin "8") (pinfunction "4D_8") (pintype "input"))
      (node (ref "IC6") (pin "8") (pinfunction "4D_8") (pintype "input"))
      (node (ref "IC8") (pin "8") (pinfunction "4D_8") (pintype "input"))
      (node (ref "IDE") (pin "10") (pinfunction "10_10") (pintype "passive"))
      (node (ref "SLOT2") (pin "10") (pinfunction "10_10") (pintype "passive"))
      (node (ref "XESS") (pin "32") (pinfunction "F2_32") (pintype "bidirectional"))
    )
    (net (code "233") (name "PB-D12") (class "Default")
      (node (ref "IC10") (pin "13") (pinfunction "5D_13") (pintype "input"))
      (node (ref "IC12") (pin "13") (pinfunction "5D_13") (pintype "input"))
      (node (ref "IC20") (pin "13") (pinfunction "5D_13") (pintype "input"))
      (node (ref "IC4") (pin "13") (pinfunction "5D_13") (pintype "input"))
      (node (ref "IC6") (pin "13") (pinfunction "5D_13") (pintype "input"))
      (node (ref "IC8") (pin "13") (pinfunction "5D_13") (pintype "input"))
      (node (ref "IDE") (pin "12") (pinfunction "12_12") (pintype "passive"))
      (node (ref "SLOT2") (pin "12") (pinfunction "12_12") (pintype "passive"))
      (node (ref "XESS") (pin "33") (pinfunction "G4_33") (pintype "bidirectional"))
    )
    (net (code "234") (name "PB-D13") (class "Default")
      (node (ref "IC10") (pin "14") (pinfunction "6D_14") (pintype "input"))
      (node (ref "IC12") (pin "14") (pinfunction "6D_14") (pintype "input"))
      (node (ref "IC20") (pin "14") (pinfunction "6D_14") (pintype "input"))
      (node (ref "IC4") (pin "14") (pinfunction "6D_14") (pintype "input"))
      (node (ref "IC6") (pin "14") (pinfunction "6D_14") (pintype "input"))
      (node (ref "IC8") (pin "14") (pinfunction "6D_14") (pintype "input"))
      (node (ref "IDE") (pin "14") (pinfunction "14_14") (pintype "passive"))
      (node (ref "SLOT2") (pin "14") (pinfunction "14_14") (pintype "passive"))
      (node (ref "XESS") (pin "34") (pinfunction "G3_34") (pintype "bidirectional"))
    )
    (net (code "235") (name "PB-D14") (class "Default")
      (node (ref "IC10") (pin "17") (pinfunction "7D_17") (pintype "input"))
      (node (ref "IC12") (pin "17") (pinfunction "7D_17") (pintype "input"))
      (node (ref "IC20") (pin "17") (pinfunction "7D_17") (pintype "input"))
      (node (ref "IC4") (pin "17") (pinfunction "7D_17") (pintype "input"))
      (node (ref "IC6") (pin "17") (pinfunction "7D_17") (pintype "input"))
      (node (ref "IC8") (pin "17") (pinfunction "7D_17") (pintype "input"))
      (node (ref "IDE") (pin "16") (pinfunction "16_16") (pintype "passive"))
      (node (ref "SLOT2") (pin "16") (pinfunction "16_16") (pintype "passive"))
      (node (ref "XESS") (pin "36") (pinfunction "G1_36") (pintype "bidirectional"))
    )
    (net (code "236") (name "PB-D15") (class "Default")
      (node (ref "IC10") (pin "18") (pinfunction "8D_18") (pintype "input"))
      (node (ref "IC12") (pin "18") (pinfunction "8D_18") (pintype "input"))
      (node (ref "IC20") (pin "18") (pinfunction "8D_18") (pintype "input"))
      (node (ref "IC4") (pin "18") (pinfunction "8D_18") (pintype "input"))
      (node (ref "IC6") (pin "18") (pinfunction "8D_18") (pintype "input"))
      (node (ref "IC8") (pin "18") (pinfunction "8D_18") (pintype "input"))
      (node (ref "IDE") (pin "18") (pinfunction "18_18") (pintype "passive"))
      (node (ref "SLOT2") (pin "18") (pinfunction "18_18") (pintype "passive"))
      (node (ref "XESS") (pin "37") (pinfunction "H4_37") (pintype "bidirectional"))
    )
    (net (code "237") (name "PB-RD#") (class "Default")
      (node (ref "R14") (pin "1") (pinfunction "1_1") (pintype "passive"))
      (node (ref "SLOT2") (pin "25") (pinfunction "25_25") (pintype "passive"))
      (node (ref "XESS") (pin "61") (pinfunction "P2_61") (pintype "bidirectional"))
    )
    (net (code "238") (name "PB-WR#") (class "Default")
      (node (ref "IC13") (pin "4") (pinfunction "G2A_4") (pintype "input"))
      (node (ref "R13") (pin "1") (pinfunction "1_1") (pintype "passive"))
      (node (ref "SLOT2") (pin "23") (pinfunction "23_23") (pintype "passive"))
      (node (ref "XESS") (pin "62") (pinfunction "R1_62") (pintype "bidirectional"))
    )
    (net (code "239") (name "PC0") (class "Default")
      (node (ref "E40") (pin "1") (pinfunction "1_1") (pintype "passive"))
      (node (ref "R98") (pin "2") (pinfunction "2_2") (pintype "passive"))
    )
    (net (code "240") (name "PC1") (class "Default")
      (node (ref "E40") (pin "10") (pinfunction "10_10") (pintype "passive"))
      (node (ref "R103") (pin "2") (pinfunction "2_2") (pintype "passive"))
    )
    (net (code "241") (name "PC2") (class "Default")
      (node (ref "E40") (pin "11") (pinfunction "11_11") (pintype "passive"))
      (node (ref "R108") (pin "2") (pinfunction "2_2") (pintype "passive"))
    )
    (net (code "242") (name "PC3") (class "Default")
      (node (ref "E40") (pin "24") (pinfunction "24_24") (pintype "passive"))
      (node (ref "R113") (pin "2") (pinfunction "2_2") (pintype "passive"))
    )
    (net (code "243") (name "PC4") (class "Default")
      (node (ref "E40") (pin "25") (pinfunction "25_25") (pintype "passive"))
      (node (ref "R118") (pin "2") (pinfunction "2_2") (pintype "passive"))
    )
    (net (code "244") (name "PC5") (class "Default")
      (node (ref "E40") (pin "34") (pinfunction "34_34") (pintype "passive"))
      (node (ref "R123") (pin "2") (pinfunction "2_2") (pintype "passive"))
    )
    (net (code "245") (name "PC6") (class "Default")
      (node (ref "F40") (pin "1") (pinfunction "1_1") (pintype "passive"))
      (node (ref "R67") (pin "2") (pinfunction "2_2") (pintype "passive"))
    )
    (net (code "246") (name "PC7") (class "Default")
      (node (ref "F40") (pin "10") (pinfunction "10_10") (pintype "passive"))
      (node (ref "R72") (pin "2") (pinfunction "2_2") (pintype "passive"))
    )
    (net (code "247") (name "PC8") (class "Default")
      (node (ref "F40") (pin "11") (pinfunction "11_11") (pintype "passive"))
      (node (ref "R77") (pin "2") (pinfunction "2_2") (pintype "passive"))
    )
    (net (code "248") (name "PC9") (class "Default")
      (node (ref "F40") (pin "24") (pinfunction "24_24") (pintype "passive"))
      (node (ref "R82") (pin "2") (pinfunction "2_2") (pintype "passive"))
    )
    (net (code "249") (name "PC10") (class "Default")
      (node (ref "F40") (pin "25") (pinfunction "25_25") (pintype "passive"))
      (node (ref "R87") (pin "2") (pinfunction "2_2") (pintype "passive"))
    )
    (net (code "250") (name "PC11") (class "Default")
      (node (ref "F40") (pin "34") (pinfunction "34_34") (pintype "passive"))
      (node (ref "R92") (pin "2") (pinfunction "2_2") (pintype "passive"))
    )
    (net (code "251") (name "RESET-TRIG#") (class "Default")
      (node (ref "R23") (pin "1") (pinfunction "1_1") (pintype "passive"))
      (node (ref "XESS") (pin "21") (pinfunction "D15_21") (pintype "bidirectional"))
    )
    (net (code "252") (name "RS232-RD") (class "Default")
      (node (ref "D1") (pin "C") (pinfunction "C_C") (pintype "passive"))
      (node (ref "R2") (pin "1") (pinfunction "1_1") (pintype "passive"))
      (node (ref "XESS") (pin "31") (pinfunction "G5_31") (pintype "bidirectional"))
    )
    (net (code "253") (name "RS232-RTS") (class "Default")
      (node (ref "R3") (pin "1") (pinfunction "1_1") (pintype "passive"))
      (node (ref "XESS") (pin "26") (pinfunction "F4_26") (pintype "bidirectional"))
    )
    (net (code "254") (name "RS232-TD") (class "Default")
      (node (ref "R1") (pin "1") (pinfunction "1_1") (pintype "passive"))
      (node (ref "XESS") (pin "41") (pinfunction "J2_41") (pintype "bidirectional"))
    )
    (net (code "255") (name "RTS") (class "Default")
      (node (ref "IC3") (pin "7") (pinfunction "T2OUT_7") (pintype "output"))
      (node (ref "RS-232") (pin "5") (pinfunction "5_5") (pintype "passive"))
      (node (ref "X1") (pin "8") (pinfunction "F_8") (pintype "passive"))
    )
    (net (code "256") (name "RUN") (class "Default")
      (node (ref "D40") (pin "33") (pinfunction "33_33") (pintype "passive"))
      (node (ref "R61") (pin "2") (pinfunction "2_2") (pintype "passive"))
    )
    (net (code "257") (name "RXD") (class "Default")
      (node (ref "IC3") (pin "8") (pinfunction "R2IN_8") (pintype "input"))
      (node (ref "RS-232") (pin "4") (pinfunction "4_4") (pintype "passive"))
      (node (ref "X1") (pin "3") (pinfunction "F_3") (pintype "passive"))
    )
    (net (code "258") (name "SC0") (class "Default")
      (node (ref "C40") (pin "9") (pinfunction "9_9") (pintype "passive"))
      (node (ref "R129") (pin "2") (pinfunction "2_2") (pintype "passive"))
    )
    (net (code "259") (name "SC1") (class "Default")
      (node (ref "C40") (pin "2") (pinfunction "2_2") (pintype "passive"))
      (node (ref "R131") (pin "2") (pinfunction "2_2") (pintype "passive"))
    )
    (net (code "260") (name "SC2") (class "Default")
      (node (ref "C40") (pin "23") (pinfunction "23_23") (pintype "passive"))
      (node (ref "R133") (pin "2") (pinfunction "2_2") (pintype "passive"))
    )
    (net (code "261") (name "SC3") (class "Default")
      (node (ref "C40") (pin "12") (pinfunction "12_12") (pintype "passive"))
      (node (ref "R135") (pin "2") (pinfunction "2_2") (pintype "passive"))
    )
    (net (code "262") (name "SC4") (class "Default")
      (node (ref "C40") (pin "33") (pinfunction "33_33") (pintype "passive"))
      (node (ref "R137") (pin "2") (pinfunction "2_2") (pintype "passive"))
    )
    (net (code "263") (name "SCLK") (class "Default")
      (node (ref "IC14") (pin "2") (pinfunction "CLK_2") (pintype "input"))
      (node (ref "IC15") (pin "2") (pinfunction "CLK_2") (pintype "input"))
      (node (ref "IC17") (pin "5") (pinfunction "Y3_5") (pintype "tri_state"))
      (node (ref "IC18") (pin "2") (pinfunction "CLK_2") (pintype "input"))
      (node (ref "IC2") (pin "2") (pinfunction "CLK_2") (pintype "input"))
    )
    (net (code "264") (name "SD-CD#") (class "Default")
      (node (ref "J4") (pin "10") (pinfunction "CD#_10") (pintype "output"))
      (node (ref "R4") (pin "1") (pinfunction "1_1") (pintype "passive"))
      (node (ref "XESS") (pin "4") (pinfunction "H14_4") (pintype "bidirectional"))
    )
    (net (code "265") (name "SD-CLK") (class "Default")
      (node (ref "J4") (pin "5") (pinfunction "CLK/SCLK_5") (pintype "bidirectional"))
      (node (ref "XESS") (pin "1") (pinfunction "H16_1") (pintype "bidirectional"))
    )
    (net (code "266") (name "SD-CMD") (class "Default")
      (node (ref "J4") (pin "2") (pinfunction "CMD/DI_2") (pintype "bidirectional"))
      (node (ref "XESS") (pin "45") (pinfunction "K5_45") (pintype "bidirectional"))
    )
    (net (code "267") (name "SD-DAT0") (class "Default")
      (node (ref "J4") (pin "7") (pinfunction "DAT0_7") (pintype "bidirectional"))
      (node (ref "XESS") (pin "66") (pinfunction "M10_66") (pintype "bidirectional"))
    )
    (net (code "268") (name "SD-DAT1") (class "Default")
      (node (ref "J4") (pin "8") (pinfunction "DAT1_8") (pintype "bidirectional"))
      (node (ref "XESS") (pin "67") (pinfunction "P11_67") (pintype "bidirectional"))
    )
    (net (code "269") (name "SD-DAT2") (class "Default")
      (node (ref "J4") (pin "9") (pinfunction "DAT2_9") (pintype "bidirectional"))
      (node (ref "XESS") (pin "68") (pinfunction "T12_68") (pintype "bidirectional"))
    )
    (net (code "270") (name "SD-DAT3") (class "Default")
      (node (ref "J4") (pin "1") (pinfunction "CD/DAT3_1") (pintype "bidirectional"))
      (node (ref "XESS") (pin "69") (pinfunction "R12_69") (pintype "bidirectional"))
    )
    (net (code "271") (name "SD-WP") (class "Default")
      (node (ref "J4") (pin "12") (pinfunction "WP_12") (pintype "output"))
      (node (ref "R5") (pin "1") (pinfunction "1_1") (pintype "passive"))
      (node (ref "XESS") (pin "5") (pinfunction "H13_5") (pintype "bidirectional"))
    )
    (net (code "272") (name "SDF0") (class "Default")
      (node (ref "A40") (pin "6") (pinfunction "6_6") (pintype "passive"))
      (node (ref "IC14") (pin "11") (pinfunction "A_11") (pintype "input"))
      (node (ref "R24") (pin "1") (pinfunction "1_1") (pintype "passive"))
    )
    (net (code "273") (name "SDF1") (class "Default")
      (node (ref "A40") (pin "8") (pinfunction "8_8") (pintype "passive"))
      (node (ref "IC14") (pin "12") (pinfunction "B_12") (pintype "input"))
      (node (ref "R25") (pin "1") (pinfunction "1_1") (pintype "passive"))
    )
    (net (code "274") (name "SDF2") (class "Default")
      (node (ref "A40") (pin "10") (pinfunction "10_10") (pintype "passive"))
      (node (ref "IC14") (pin "13") (pinfunction "C_13") (pintype "input"))
      (node (ref "R26") (pin "1") (pinfunction "1_1") (pintype "passive"))
    )
    (net (code "275") (name "SI") (class "Default")
      (node (ref "B40") (pin "32") (pinfunction "32_32") (pintype "passive"))
      (node (ref "IC18") (pin "12") (pinfunction "B_12") (pintype "input"))
      (node (ref "R49") (pin "1") (pinfunction "1_1") (pintype "passive"))
    )
    (net (code "276") (name "SIF0") (class "Default")
      (node (ref "A40") (pin "12") (pinfunction "12_12") (pintype "passive"))
      (node (ref "IC14") (pin "14") (pinfunction "D_14") (pintype "input"))
      (node (ref "R27") (pin "1") (pinfunction "1_1") (pintype "passive"))
    )
    (net (code "277") (name "SIF1") (class "Default")
      (node (ref "A40") (pin "14") (pinfunction "14_14") (pintype "passive"))
      (node (ref "IC14") (pin "3") (pinfunction "E_3") (pintype "input"))
      (node (ref "R28") (pin "1") (pinfunction "1_1") (pintype "passive"))
    )
    (net (code "278") (name "SIF2") (class "Default")
      (node (ref "A40") (pin "16") (pinfunction "16_16") (pintype "passive"))
      (node (ref "IC14") (pin "4") (pinfunction "F_4") (pintype "input"))
      (node (ref "R29") (pin "1") (pinfunction "1_1") (pintype "passive"))
    )
    (net (code "279") (name "SLOT1-CS#") (class "Default")
      (node (ref "IC13") (pin "5") (pinfunction "G2B_5") (pintype "input"))
      (node (ref "XESS") (pin "18") (pinfunction "E15_18") (pintype "bidirectional"))
    )
    (net (code "280") (name "SLOT1-IRQ") (class "Default")
      (node (ref "XESS") (pin "84") (pinfunction "J16_84") (pintype "bidirectional"))
    )
    (net (code "281") (name "SLOT2-CS#") (class "Default")
      (node (ref "SLOT2") (pin "37") (pinfunction "37_37") (pintype "passive"))
      (node (ref "XESS") (pin "19") (pinfunction "D16_19") (pintype "bidirectional"))
    )
    (net (code "282") (name "SLOT2-IRQ") (class "Default")
      (node (ref "R22") (pin "1") (pinfunction "1_1") (pintype "passive"))
      (node (ref "XESS") (pin "83") (pinfunction "J14_83") (pintype "bidirectional"))
    )
    (net (code "283") (name "SR0") (class "Default")
      (node (ref "A40") (pin "18") (pinfunction "18_18") (pintype "passive"))
      (node (ref "IC14") (pin "5") (pinfunction "G_5") (pintype "input"))
      (node (ref "R30") (pin "1") (pinfunction "1_1") (pintype "passive"))
    )
    (net (code "284") (name "SR1") (class "Default")
      (node (ref "A40") (pin "20") (pinfunction "20_20") (pintype "passive"))
      (node (ref "IC14") (pin "6") (pinfunction "H_6") (pintype "input"))
      (node (ref "R31") (pin "1") (pinfunction "1_1") (pintype "passive"))
    )
    (net (code "285") (name "SR2") (class "Default")
      (node (ref "A40") (pin "26") (pinfunction "26_26") (pintype "passive"))
      (node (ref "IC15") (pin "11") (pinfunction "A_11") (pintype "input"))
      (node (ref "R32") (pin "1") (pinfunction "1_1") (pintype "passive"))
    )
    (net (code "286") (name "SR3") (class "Default")
      (node (ref "A40") (pin "28") (pinfunction "28_28") (pintype "passive"))
      (node (ref "IC15") (pin "12") (pinfunction "B_12") (pintype "input"))
      (node (ref "R33") (pin "1") (pinfunction "1_1") (pintype "passive"))
    )
    (net (code "287") (name "SR4") (class "Default")
      (node (ref "A40") (pin "30") (pinfunction "30_30") (pintype "passive"))
      (node (ref "IC15") (pin "13") (pinfunction "C_13") (pintype "input"))
      (node (ref "R34") (pin "1") (pinfunction "1_1") (pintype "passive"))
    )
    (net (code "288") (name "SR5") (class "Default")
      (node (ref "A40") (pin "34") (pinfunction "34_34") (pintype "passive"))
      (node (ref "IC15") (pin "14") (pinfunction "D_14") (pintype "input"))
      (node (ref "R35") (pin "1") (pinfunction "1_1") (pintype "passive"))
    )
    (net (code "289") (name "SR6") (class "Default")
      (node (ref "A40") (pin "32") (pinfunction "32_32") (pintype "passive"))
      (node (ref "IC15") (pin "3") (pinfunction "E_3") (pintype "input"))
      (node (ref "R36") (pin "1") (pinfunction "1_1") (pintype "passive"))
    )
    (net (code "290") (name "SR7") (class "Default")
      (node (ref "B40") (pin "6") (pinfunction "6_6") (pintype "passive"))
      (node (ref "IC15") (pin "4") (pinfunction "F_4") (pintype "input"))
      (node (ref "R37") (pin "1") (pinfunction "1_1") (pintype "passive"))
    )
    (net (code "291") (name "SR8") (class "Default")
      (node (ref "B40") (pin "8") (pinfunction "8_8") (pintype "passive"))
      (node (ref "IC15") (pin "5") (pinfunction "G_5") (pintype "input"))
      (node (ref "R38") (pin "1") (pinfunction "1_1") (pintype "passive"))
    )
    (net (code "292") (name "SR9") (class "Default")
      (node (ref "B40") (pin "10") (pinfunction "10_10") (pintype "passive"))
      (node (ref "IC15") (pin "6") (pinfunction "H_6") (pintype "input"))
      (node (ref "R39") (pin "1") (pinfunction "1_1") (pintype "passive"))
    )
    (net (code "293") (name "SR10") (class "Default")
      (node (ref "B40") (pin "12") (pinfunction "12_12") (pintype "passive"))
      (node (ref "IC2") (pin "11") (pinfunction "A_11") (pintype "input"))
      (node (ref "R40") (pin "1") (pinfunction "1_1") (pintype "passive"))
    )
    (net (code "294") (name "SR11") (class "Default")
      (node (ref "B40") (pin "14") (pinfunction "14_14") (pintype "passive"))
      (node (ref "IC2") (pin "12") (pinfunction "B_12") (pintype "input"))
      (node (ref "R41") (pin "1") (pinfunction "1_1") (pintype "passive"))
    )
    (net (code "295") (name "SS") (class "Default")
      (node (ref "B40") (pin "34") (pinfunction "34_34") (pintype "passive"))
      (node (ref "IC18") (pin "11") (pinfunction "A_11") (pintype "input"))
      (node (ref "R48") (pin "1") (pinfunction "1_1") (pintype "passive"))
    )
    (net (code "296") (name "START") (class "Default")
      (node (ref "B40") (pin "16") (pinfunction "16_16") (pintype "passive"))
      (node (ref "IC2") (pin "13") (pinfunction "C_13") (pintype "input"))
      (node (ref "R42") (pin "1") (pinfunction "1_1") (pintype "passive"))
    )
    (net (code "297") (name "STOP") (class "Default")
      (node (ref "B40") (pin "30") (pinfunction "30_30") (pintype "passive"))
      (node (ref "IC2") (pin "6") (pinfunction "H_6") (pintype "input"))
      (node (ref "R47") (pin "1") (pinfunction "1_1") (pintype "passive"))
    )
    (net (code "298") (name "TAD") (class "Default")
      (node (ref "D40") (pin "4") (pinfunction "4_4") (pintype "passive"))
      (node (ref "R53") (pin "2") (pinfunction "2_2") (pintype "passive"))
    )
    (net (code "299") (name "TXD") (class "Default")
      (node (ref "IC3") (pin "13") (pinfunction "R1IN_13") (pintype "input"))
      (node (ref "IC3") (pin "14") (pinfunction "T1OUT_14") (pintype "output"))
      (node (ref "RS-232") (pin "2") (pinfunction "2_2") (pintype "passive"))
      (node (ref "X1") (pin "2") (pinfunction "F_2") (pintype "passive"))
    )
    (net (code "300") (name "VCC") (class "Default")
      (node (ref "+V1") (pin "1") (pinfunction "1_1") (pintype "passive"))
      (node (ref "+V2") (pin "1") (pinfunction "1_1") (pintype "passive"))
      (node (ref "+V3") (pin "1") (pinfunction "1_1") (pintype "passive"))
      (node (ref "+V4") (pin "1") (pinfunction "1_1") (pintype "passive"))
      (node (ref "5V") (pin "1") (pinfunction "1_1") (pintype "passive"))
      (node (ref "C1") (pin "1") (pinfunction "1_1") (pintype "passive"))
      (node (ref "C10") (pin "1") (pinfunction "1_1") (pintype "passive"))
      (node (ref "C11") (pin "1") (pinfunction "1_1") (pintype "passive"))
      (node (ref "C12") (pin "1") (pinfunction "1_1") (pintype "passive"))
      (node (ref "C13") (pin "1") (pinfunction "1_1") (pintype "passive"))
      (node (ref "C14") (pin "1") (pinfunction "1_1") (pintype "passive"))
      (node (ref "C15") (pin "1") (pinfunction "1_1") (pintype "passive"))
      (node (ref "C16") (pin "1") (pinfunction "1_1") (pintype "passive"))
      (node (ref "C17") (pin "1") (pinfunction "1_1") (pintype "passive"))
      (node (ref "C18") (pin "1") (pinfunction "1_1") (pintype "passive"))
      (node (ref "C19") (pin "1") (pinfunction "1_1") (pintype "passive"))
      (node (ref "C20") (pin "1") (pinfunction "1_1") (pintype "passive"))
      (node (ref "C21") (pin "1") (pinfunction "1_1") (pintype "passive"))
      (node (ref "C22") (pin "1") (pinfunction "1_1") (pintype "passive"))
      (node (ref "C23") (pin "1") (pinfunction "1_1") (pintype "passive"))
      (node (ref "C24") (pin "1") (pinfunction "1_1") (pintype "passive"))
      (node (ref "C6") (pin "1") (pinfunction "1_1") (pintype "passive"))
      (node (ref "C7") (pin "1") (pinfunction "1_1") (pintype "passive"))
      (node (ref "C8") (pin "1") (pinfunction "1_1") (pintype "passive"))
      (node (ref "C9") (pin "1") (pinfunction "1_1") (pintype "passive"))
      (node (ref "IC13") (pin "6") (pinfunction "G1_6") (pintype "input"))
      (node (ref "J1") (pin "4") (pinfunction "4_4") (pintype "passive"))
      (node (ref "R10") (pin "1") (pinfunction "1_1") (pintype "passive"))
      (node (ref "R24") (pin "2") (pinfunction "2_2") (pintype "passive"))
      (node (ref "R25") (pin "2") (pinfunction "2_2") (pintype "passive"))
      (node (ref "R26") (pin "2") (pinfunction "2_2") (pintype "passive"))
      (node (ref "R27") (pin "2") (pinfunction "2_2") (pintype "passive"))
      (node (ref "R28") (pin "2") (pinfunction "2_2") (pintype "passive"))
      (node (ref "R29") (pin "2") (pinfunction "2_2") (pintype "passive"))
      (node (ref "R30") (pin "2") (pinfunction "2_2") (pintype "passive"))
      (node (ref "R31") (pin "2") (pinfunction "2_2") (pintype "passive"))
      (node (ref "R32") (pin "2") (pinfunction "2_2") (pintype "passive"))
      (node (ref "R33") (pin "2") (pinfunction "2_2") (pintype "passive"))
      (node (ref "R34") (pin "2") (pinfunction "2_2") (pintype "passive"))
      (node (ref "R35") (pin "2") (pinfunction "2_2") (pintype "passive"))
      (node (ref "R36") (pin "2") (pinfunction "2_2") (pintype "passive"))
      (node (ref "R37") (pin "2") (pinfunction "2_2") (pintype "passive"))
      (node (ref "R38") (pin "2") (pinfunction "2_2") (pintype "passive"))
      (node (ref "R39") (pin "2") (pinfunction "2_2") (pintype "passive"))
      (node (ref "R40") (pin "2") (pinfunction "2_2") (pintype "passive"))
      (node (ref "R41") (pin "2") (pinfunction "2_2") (pintype "passive"))
      (node (ref "R42") (pin "2") (pinfunction "2_2") (pintype "passive"))
      (node (ref "R43") (pin "2") (pinfunction "2_2") (pintype "passive"))
      (node (ref "R44") (pin "2") (pinfunction "2_2") (pintype "passive"))
      (node (ref "R45") (pin "2") (pinfunction "2_2") (pintype "passive"))
      (node (ref "R46") (pin "2") (pinfunction "2_2") (pintype "passive"))
      (node (ref "R47") (pin "2") (pinfunction "2_2") (pintype "passive"))
      (node (ref "R48") (pin "2") (pinfunction "2_2") (pintype "passive"))
      (node (ref "R49") (pin "2") (pinfunction "2_2") (pintype "passive"))
      (node (ref "R50") (pin "1") (pinfunction "1_1") (pintype "passive"))
      (node (ref "R6") (pin "1") (pinfunction "1_1") (pintype "passive"))
      (node (ref "R7") (pin "1") (pinfunction "1_1") (pintype "passive"))
      (node (ref "R8") (pin "1") (pinfunction "1_1") (pintype "passive"))
      (node (ref "R9") (pin "1") (pinfunction "1_1") (pintype "passive"))
    )
    (net (code "301") (name "VDD") (class "Default")
      (node (ref "3.3V") (pin "2") (pinfunction "2_2") (pintype "passive"))
      (node (ref "J4") (pin "4") (pinfunction "VDD_4") (pintype "power_in"))
    )
    (net (code "302") (name "VSS") (class "Default")
      (node (ref "J3") (pin "1") (pinfunction "1_1") (pintype "passive"))
      (node (ref "J4") (pin "3") (pinfunction "VSS_3") (pintype "power_in"))
      (node (ref "J4") (pin "6") (pinfunction "VSS_6") (pintype "power_in"))
    )
    (net (code "303") (name "WC") (class "Default")
      (node (ref "D40") (pin "30") (pinfunction "30_30") (pintype "passive"))
      (node (ref "R64") (pin "2") (pinfunction "2_2") (pintype "passive"))
    )
    (net (code "304") (name "unconnected-(A40-Pad1)") (class "Default")
      (node (ref "A40") (pin "1") (pinfunction "1_1") (pintype "passive"))
    )
    (net (code "305") (name "unconnected-(A40-Pad2)") (class "Default")
      (node (ref "A40") (pin "2") (pinfunction "2_2") (pintype "passive"))
    )
    (net (code "306") (name "unconnected-(A40-Pad3)") (class "Default")
      (node (ref "A40") (pin "3") (pinfunction "3_3") (pintype "passive"))
    )
    (net (code "307") (name "unconnected-(A40-Pad5)") (class "Default")
      (node (ref "A40") (pin "5") (pinfunction "5_5") (pintype "passive"))
    )
    (net (code "308") (name "unconnected-(A40-Pad7)") (class "Default")
      (node (ref "A40") (pin "7") (pinfunction "7_7") (pintype "passive"))
    )
    (net (code "309") (name "unconnected-(A40-Pad9)") (class "Default")
      (node (ref "A40") (pin "9") (pinfunction "9_9") (pintype "passive"))
    )
    (net (code "310") (name "unconnected-(A40-Pad11)") (class "Default")
      (node (ref "A40") (pin "11") (pinfunction "11_11") (pintype "passive"))
    )
    (net (code "311") (name "unconnected-(A40-Pad13)") (class "Default")
      (node (ref "A40") (pin "13") (pinfunction "13_13") (pintype "passive"))
    )
    (net (code "312") (name "unconnected-(A40-Pad15)") (class "Default")
      (node (ref "A40") (pin "15") (pinfunction "15_15") (pintype "passive"))
    )
    (net (code "313") (name "unconnected-(A40-Pad17)") (class "Default")
      (node (ref "A40") (pin "17") (pinfunction "17_17") (pintype "passive"))
    )
    (net (code "314") (name "unconnected-(A40-Pad19)") (class "Default")
      (node (ref "A40") (pin "19") (pinfunction "19_19") (pintype "passive"))
    )
    (net (code "315") (name "unconnected-(A40-Pad21)") (class "Default")
      (node (ref "A40") (pin "21") (pinfunction "21_21") (pintype "passive"))
    )
    (net (code "316") (name "unconnected-(A40-Pad22)") (class "Default")
      (node (ref "A40") (pin "22") (pinfunction "22_22") (pintype "passive"))
    )
    (net (code "317") (name "unconnected-(A40-Pad23)") (class "Default")
      (node (ref "A40") (pin "23") (pinfunction "23_23") (pintype "passive"))
    )
    (net (code "318") (name "unconnected-(A40-Pad24)") (class "Default")
      (node (ref "A40") (pin "24") (pinfunction "24_24") (pintype "passive"))
    )
    (net (code "319") (name "unconnected-(A40-Pad25)") (class "Default")
      (node (ref "A40") (pin "25") (pinfunction "25_25") (pintype "passive"))
    )
    (net (code "320") (name "unconnected-(A40-Pad27)") (class "Default")
      (node (ref "A40") (pin "27") (pinfunction "27_27") (pintype "passive"))
    )
    (net (code "321") (name "unconnected-(A40-Pad29)") (class "Default")
      (node (ref "A40") (pin "29") (pinfunction "29_29") (pintype "passive"))
    )
    (net (code "322") (name "unconnected-(A40-Pad31)") (class "Default")
      (node (ref "A40") (pin "31") (pinfunction "31_31") (pintype "passive"))
    )
    (net (code "323") (name "unconnected-(A40-Pad33)") (class "Default")
      (node (ref "A40") (pin "33") (pinfunction "33_33") (pintype "passive"))
    )
    (net (code "324") (name "unconnected-(B40-Pad1)") (class "Default")
      (node (ref "B40") (pin "1") (pinfunction "1_1") (pintype "passive"))
    )
    (net (code "325") (name "unconnected-(B40-Pad2)") (class "Default")
      (node (ref "B40") (pin "2") (pinfunction "2_2") (pintype "passive"))
    )
    (net (code "326") (name "unconnected-(B40-Pad3)") (class "Default")
      (node (ref "B40") (pin "3") (pinfunction "3_3") (pintype "passive"))
    )
    (net (code "327") (name "unconnected-(B40-Pad5)") (class "Default")
      (node (ref "B40") (pin "5") (pinfunction "5_5") (pintype "passive"))
    )
    (net (code "328") (name "unconnected-(B40-Pad7)") (class "Default")
      (node (ref "B40") (pin "7") (pinfunction "7_7") (pintype "passive"))
    )
    (net (code "329") (name "unconnected-(B40-Pad9)") (class "Default")
      (node (ref "B40") (pin "9") (pinfunction "9_9") (pintype "passive"))
    )
    (net (code "330") (name "unconnected-(B40-Pad11)") (class "Default")
      (node (ref "B40") (pin "11") (pinfunction "11_11") (pintype "passive"))
    )
    (net (code "331") (name "unconnected-(B40-Pad13)") (class "Default")
      (node (ref "B40") (pin "13") (pinfunction "13_13") (pintype "passive"))
    )
    (net (code "332") (name "unconnected-(B40-Pad15)") (class "Default")
      (node (ref "B40") (pin "15") (pinfunction "15_15") (pintype "passive"))
    )
    (net (code "333") (name "unconnected-(B40-Pad17)") (class "Default")
      (node (ref "B40") (pin "17") (pinfunction "17_17") (pintype "passive"))
    )
    (net (code "334") (name "unconnected-(B40-Pad19)") (class "Default")
      (node (ref "B40") (pin "19") (pinfunction "19_19") (pintype "passive"))
    )
    (net (code "335") (name "unconnected-(B40-Pad21)") (class "Default")
      (node (ref "B40") (pin "21") (pinfunction "21_21") (pintype "passive"))
    )
    (net (code "336") (name "unconnected-(B40-Pad22)") (class "Default")
      (node (ref "B40") (pin "22") (pinfunction "22_22") (pintype "passive"))
    )
    (net (code "337") (name "unconnected-(B40-Pad23)") (class "Default")
      (node (ref "B40") (pin "23") (pinfunction "23_23") (pintype "passive"))
    )
    (net (code "338") (name "unconnected-(B40-Pad24)") (class "Default")
      (node (ref "B40") (pin "24") (pinfunction "24_24") (pintype "passive"))
    )
    (net (code "339") (name "unconnected-(B40-Pad25)") (class "Default")
      (node (ref "B40") (pin "25") (pinfunction "25_25") (pintype "passive"))
    )
    (net (code "340") (name "unconnected-(B40-Pad27)") (class "Default")
      (node (ref "B40") (pin "27") (pinfunction "27_27") (pintype "passive"))
    )
    (net (code "341") (name "unconnected-(B40-Pad29)") (class "Default")
      (node (ref "B40") (pin "29") (pinfunction "29_29") (pintype "passive"))
    )
    (net (code "342") (name "unconnected-(B40-Pad31)") (class "Default")
      (node (ref "B40") (pin "31") (pinfunction "31_31") (pintype "passive"))
    )
    (net (code "343") (name "unconnected-(B40-Pad33)") (class "Default")
      (node (ref "B40") (pin "33") (pinfunction "33_33") (pintype "passive"))
    )
    (net (code "344") (name "unconnected-(C40-Pad3)") (class "Default")
      (node (ref "C40") (pin "3") (pinfunction "3_3") (pintype "passive"))
    )
    (net (code "345") (name "unconnected-(C40-Pad4)") (class "Default")
      (node (ref "C40") (pin "4") (pinfunction "4_4") (pintype "passive"))
    )
    (net (code "346") (name "unconnected-(C40-Pad5)") (class "Default")
      (node (ref "C40") (pin "5") (pinfunction "5_5") (pintype "passive"))
    )
    (net (code "347") (name "unconnected-(C40-Pad6)") (class "Default")
      (node (ref "C40") (pin "6") (pinfunction "6_6") (pintype "passive"))
    )
    (net (code "348") (name "unconnected-(C40-Pad7)") (class "Default")
      (node (ref "C40") (pin "7") (pinfunction "7_7") (pintype "passive"))
    )
    (net (code "349") (name "unconnected-(C40-Pad8)") (class "Default")
      (node (ref "C40") (pin "8") (pinfunction "8_8") (pintype "passive"))
    )
    (net (code "350") (name "unconnected-(C40-Pad13)") (class "Default")
      (node (ref "C40") (pin "13") (pinfunction "13_13") (pintype "passive"))
    )
    (net (code "351") (name "unconnected-(C40-Pad14)") (class "Default")
      (node (ref "C40") (pin "14") (pinfunction "14_14") (pintype "passive"))
    )
    (net (code "352") (name "unconnected-(C40-Pad15)") (class "Default")
      (node (ref "C40") (pin "15") (pinfunction "15_15") (pintype "passive"))
    )
    (net (code "353") (name "unconnected-(C40-Pad16)") (class "Default")
      (node (ref "C40") (pin "16") (pinfunction "16_16") (pintype "passive"))
    )
    (net (code "354") (name "unconnected-(C40-Pad21)") (class "Default")
      (node (ref "C40") (pin "21") (pinfunction "21_21") (pintype "passive"))
    )
    (net (code "355") (name "unconnected-(C40-Pad22)") (class "Default")
      (node (ref "C40") (pin "22") (pinfunction "22_22") (pintype "passive"))
    )
    (net (code "356") (name "unconnected-(C40-Pad26)") (class "Default")
      (node (ref "C40") (pin "26") (pinfunction "26_26") (pintype "passive"))
    )
    (net (code "357") (name "unconnected-(C40-Pad27)") (class "Default")
      (node (ref "C40") (pin "27") (pinfunction "27_27") (pintype "passive"))
    )
    (net (code "358") (name "unconnected-(C40-Pad29)") (class "Default")
      (node (ref "C40") (pin "29") (pinfunction "29_29") (pintype "passive"))
    )
    (net (code "359") (name "unconnected-(C40-Pad30)") (class "Default")
      (node (ref "C40") (pin "30") (pinfunction "30_30") (pintype "passive"))
    )
    (net (code "360") (name "unconnected-(C40-Pad31)") (class "Default")
      (node (ref "C40") (pin "31") (pinfunction "31_31") (pintype "passive"))
    )
    (net (code "361") (name "unconnected-(C40-Pad32)") (class "Default")
      (node (ref "C40") (pin "32") (pinfunction "32_32") (pintype "passive"))
    )
    (net (code "362") (name "unconnected-(CONFIGSW-Pad7)") (class "Default")
      (node (ref "CONFIGSW") (pin "7") (pinfunction "7_7") (pintype "passive"))
    )
    (net (code "363") (name "unconnected-(CONFIGSW-Pad8)") (class "Default")
      (node (ref "CONFIGSW") (pin "8") (pinfunction "8_8") (pintype "passive"))
    )
    (net (code "364") (name "unconnected-(CONFIGSW-Pad9)") (class "Default")
      (node (ref "CONFIGSW") (pin "9") (pinfunction "9_9") (pintype "passive"))
    )
    (net (code "365") (name "unconnected-(D40-Pad1)") (class "Default")
      (node (ref "D40") (pin "1") (pinfunction "1_1") (pintype "passive"))
    )
    (net (code "366") (name "unconnected-(D40-Pad3)") (class "Default")
      (node (ref "D40") (pin "3") (pinfunction "3_3") (pintype "passive"))
    )
    (net (code "367") (name "unconnected-(D40-Pad5)") (class "Default")
      (node (ref "D40") (pin "5") (pinfunction "5_5") (pintype "passive"))
    )
    (net (code "368") (name "unconnected-(D40-Pad7)") (class "Default")
      (node (ref "D40") (pin "7") (pinfunction "7_7") (pintype "passive"))
    )
    (net (code "369") (name "unconnected-(D40-Pad9)") (class "Default")
      (node (ref "D40") (pin "9") (pinfunction "9_9") (pintype "passive"))
    )
    (net (code "370") (name "unconnected-(D40-Pad11)") (class "Default")
      (node (ref "D40") (pin "11") (pinfunction "11_11") (pintype "passive"))
    )
    (net (code "371") (name "unconnected-(D40-Pad13)") (class "Default")
      (node (ref "D40") (pin "13") (pinfunction "13_13") (pintype "passive"))
    )
    (net (code "372") (name "unconnected-(D40-Pad14)") (class "Default")
      (node (ref "D40") (pin "14") (pinfunction "14_14") (pintype "passive"))
    )
    (net (code "373") (name "unconnected-(D40-Pad15)") (class "Default")
      (node (ref "D40") (pin "15") (pinfunction "15_15") (pintype "passive"))
    )
    (net (code "374") (name "unconnected-(D40-Pad21)") (class "Default")
      (node (ref "D40") (pin "21") (pinfunction "21_21") (pintype "passive"))
    )
    (net (code "375") (name "unconnected-(D40-Pad25)") (class "Default")
      (node (ref "D40") (pin "25") (pinfunction "25_25") (pintype "passive"))
    )
    (net (code "376") (name "unconnected-(D40-Pad27)") (class "Default")
      (node (ref "D40") (pin "27") (pinfunction "27_27") (pintype "passive"))
    )
    (net (code "377") (name "unconnected-(D40-Pad29)") (class "Default")
      (node (ref "D40") (pin "29") (pinfunction "29_29") (pintype "passive"))
    )
    (net (code "378") (name "unconnected-(IC2A-~{QH}-Pad7)") (class "Default")
      (node (ref "IC2") (pin "7") (pinfunction "~{QH}_7") (pintype "output"))
    )
    (net (code "379") (name "unconnected-(IC3A-R1OUT-Pad12)") (class "Default")
      (node (ref "IC3") (pin "12") (pinfunction "R1OUT_12") (pintype "output"))
    )
    (net (code "380") (name "unconnected-(IC6A-7Q-Pad16)") (class "Default")
      (node (ref "IC6") (pin "16") (pinfunction "7Q_16") (pintype "tri_state"))
    )
    (net (code "381") (name "unconnected-(IC6A-8Q-Pad19)") (class "Default")
      (node (ref "IC6") (pin "19") (pinfunction "8Q_19") (pintype "tri_state"))
    )
    (net (code "382") (name "unconnected-(IC10A-7Q-Pad16)") (class "Default")
      (node (ref "IC10") (pin "16") (pinfunction "7Q_16") (pintype "tri_state"))
    )
    (net (code "383") (name "unconnected-(IC13A-Y6-Pad9)") (class "Default")
      (node (ref "IC13") (pin "9") (pinfunction "Y6_9") (pintype "output"))
    )
    (net (code "384") (name "unconnected-(IC13A-Y7-Pad7)") (class "Default")
      (node (ref "IC13") (pin "7") (pinfunction "Y7_7") (pintype "output"))
    )
    (net (code "385") (name "unconnected-(IC14A-~{QH}-Pad7)") (class "Default")
      (node (ref "IC14") (pin "7") (pinfunction "~{QH}_7") (pintype "output"))
    )
    (net (code "386") (name "unconnected-(IC15A-~{QH}-Pad7)") (class "Default")
      (node (ref "IC15") (pin "7") (pinfunction "~{QH}_7") (pintype "output"))
    )
    (net (code "387") (name "unconnected-(IC18A-~{QH}-Pad7)") (class "Default")
      (node (ref "IC18") (pin "7") (pinfunction "~{QH}_7") (pintype "output"))
    )
    (net (code "388") (name "unconnected-(IC20A-5Q-Pad12)") (class "Default")
      (node (ref "IC20") (pin "12") (pinfunction "5Q_12") (pintype "tri_state"))
    )
    (net (code "389") (name "unconnected-(IC20A-6Q-Pad15)") (class "Default")
      (node (ref "IC20") (pin "15") (pinfunction "6Q_15") (pintype "tri_state"))
    )
    (net (code "390") (name "unconnected-(IC20A-7Q-Pad16)") (class "Default")
      (node (ref "IC20") (pin "16") (pinfunction "7Q_16") (pintype "tri_state"))
    )
    (net (code "391") (name "unconnected-(IC20A-8Q-Pad19)") (class "Default")
      (node (ref "IC20") (pin "19") (pinfunction "8Q_19") (pintype "tri_state"))
    )
    (net (code "392") (name "unconnected-(IDE-Pad20)") (class "Default")
      (node (ref "IDE") (pin "20") (pinfunction "20_20") (pintype "passive"))
    )
    (net (code "393") (name "unconnected-(IDE-Pad32)") (class "Default")
      (node (ref "IDE") (pin "32") (pinfunction "32_32") (pintype "passive"))
    )
    (net (code "394") (name "unconnected-(IDE-Pad34)") (class "Default")
      (node (ref "IDE") (pin "34") (pinfunction "34_34") (pintype "passive"))
    )
    (net (code "395") (name "unconnected-(IDE-Pad39)") (class "Default")
      (node (ref "IDE") (pin "39") (pinfunction "39_39") (pintype "passive"))
    )
    (net (code "396") (name "unconnected-(RS-232-Pad1)") (class "Default")
      (node (ref "RS-232") (pin "1") (pinfunction "1_1") (pintype "passive"))
    )
    (net (code "397") (name "unconnected-(SLOT2-Pad34)") (class "Default")
      (node (ref "SLOT2") (pin "34") (pinfunction "34_34") (pintype "passive"))
    )
    (net (code "398") (name "unconnected-(XESS-BSY-Pad17)") (class "Default")
      (node (ref "XESS") (pin "17") (pinfunction "BSY_17") (pintype "bidirectional"))
    )
    (net (code "399") (name "unconnected-(XESS-CLKB-Pad11)") (class "Default")
      (node (ref "XESS") (pin "11") (pinfunction "CLKB_11") (pintype "bidirectional"))
    )
    (net (code "400") (name "unconnected-(XESS-CLKC-Pad64)") (class "Default")
      (node (ref "XESS") (pin "64") (pinfunction "CLKC_64") (pintype "bidirectional"))
    )
    (net (code "401") (name "unconnected-(XESS-CS#-Pad15)") (class "Default")
      (node (ref "XESS") (pin "15") (pinfunction "CS#_15") (pintype "bidirectional"))
    )
    (net (code "402") (name "unconnected-(XESS-D1-Pad25)") (class "Default")
      (node (ref "XESS") (pin "25") (pinfunction "D1_25") (pintype "bidirectional"))
    )
    (net (code "403") (name "unconnected-(XESS-E14-Pad20)") (class "Default")
      (node (ref "XESS") (pin "20") (pinfunction "E14_20") (pintype "bidirectional"))
    )
    (net (code "404") (name "unconnected-(XESS-G13-Pad9)") (class "Default")
      (node (ref "XESS") (pin "9") (pinfunction "G13_9") (pintype "bidirectional"))
    )
    (net (code "405") (name "unconnected-(XESS-G16-Pad6)") (class "Default")
      (node (ref "XESS") (pin "6") (pinfunction "G16_6") (pintype "bidirectional"))
    )
    (net (code "406") (name "unconnected-(XESS-J3-Pad42)") (class "Default")
      (node (ref "XESS") (pin "42") (pinfunction "J3_42") (pintype "bidirectional"))
    )
    (net (code "407") (name "unconnected-(XESS-J13-Pad82)") (class "Default")
      (node (ref "XESS") (pin "82") (pinfunction "J13_82") (pintype "bidirectional"))
    )
    (net (code "408") (name "unconnected-(XESS-L3-Pad46)") (class "Default")
      (node (ref "XESS") (pin "46") (pinfunction "L3_46") (pintype "bidirectional"))
    )
    (net (code "409") (name "unconnected-(XESS-L15-Pad79)") (class "Default")
      (node (ref "XESS") (pin "79") (pinfunction "L15_79") (pintype "bidirectional"))
    )
    (net (code "410") (name "unconnected-(XESS-M1-Pad47)") (class "Default")
      (node (ref "XESS") (pin "47") (pinfunction "M1_47") (pintype "bidirectional"))
    )
    (net (code "411") (name "unconnected-(XESS-M2-Pad48)") (class "Default")
      (node (ref "XESS") (pin "48") (pinfunction "M2_48") (pintype "bidirectional"))
    )
    (net (code "412") (name "unconnected-(XESS-N15-Pad77)") (class "Default")
      (node (ref "XESS") (pin "77") (pinfunction "N15_77") (pintype "bidirectional"))
    )
    (net (code "413") (name "unconnected-(XESS-P$53-Pad53)") (class "Default")
      (node (ref "XESS") (pin "53") (pinfunction "P$53_53") (pintype "bidirectional"))
    )
    (net (code "414") (name "unconnected-(XESS-P$63-Pad63)") (class "Default")
      (node (ref "XESS") (pin "63") (pinfunction "P$63_63") (pintype "bidirectional"))
    )
    (net (code "415") (name "unconnected-(XESS-P$65-Pad65)") (class "Default")
      (node (ref "XESS") (pin "65") (pinfunction "P$65_65") (pintype "bidirectional"))
    )
    (net (code "416") (name "unconnected-(XESS-P$72-Pad72)") (class "Default")
      (node (ref "XESS") (pin "72") (pinfunction "P$72_72") (pintype "bidirectional"))
    )
    (net (code "417") (name "unconnected-(XESS-P$73-Pad73)") (class "Default")
      (node (ref "XESS") (pin "73") (pinfunction "P$73_73") (pintype "bidirectional"))
    )
    (net (code "418") (name "unconnected-(XESS-P$74-Pad74)") (class "Default")
      (node (ref "XESS") (pin "74") (pinfunction "P$74_74") (pintype "bidirectional"))
    )
    (net (code "419") (name "unconnected-(XESS-P$75-Pad75)") (class "Default")
      (node (ref "XESS") (pin "75") (pinfunction "P$75_75") (pintype "bidirectional"))
    )
    (net (code "420") (name "unconnected-(XESS-P$76-Pad76)") (class "Default")
      (node (ref "XESS") (pin "76") (pinfunction "P$76_76") (pintype "bidirectional"))
    )
    (net (code "421") (name "unconnected-(XESS-PROG#-Pad55)") (class "Default")
      (node (ref "XESS") (pin "55") (pinfunction "PROG#_55") (pintype "bidirectional"))
    )
    (net (code "422") (name "unconnected-(XESS-TCK-Pad16)") (class "Default")
      (node (ref "XESS") (pin "16") (pinfunction "TCK_16") (pintype "bidirectional"))
    )
    (net (code "423") (name "unconnected-(XESS-WR#-Pad30)") (class "Default")
      (node (ref "XESS") (pin "30") (pinfunction "WR#_30") (pintype "bidirectional"))
    )
    (net (code "424") (name "~{3S-LCL}") (class "Default")
      (node (ref "IC17") (pin "11") (pinfunction "A1_11") (pintype "input"))
      (node (ref "XESS") (pin "78") (pinfunction "M15_78") (pintype "bidirectional"))
    )
    (net (code "425") (name "~{3S-SCL}") (class "Default")
      (node (ref "IC17") (pin "8") (pinfunction "A4_8") (pintype "input"))
      (node (ref "XESS") (pin "60") (pinfunction "N3_60") (pintype "bidirectional"))
    )
    (net (code "426") (name "~{LCL}") (class "Default")
      (node (ref "IC17") (pin "9") (pinfunction "Y1_9") (pintype "tri_state"))
    )
    (net (code "427") (name "~{SCL}") (class "Default")
      (node (ref "IC14") (pin "1") (pinfunction "SH/~{LD}_1") (pintype "input"))
      (node (ref "IC15") (pin "1") (pinfunction "SH/~{LD}_1") (pintype "input"))
      (node (ref "IC17") (pin "12") (pinfunction "Y4_12") (pintype "tri_state"))
      (node (ref "IC18") (pin "1") (pinfunction "SH/~{LD}_1") (pintype "input"))
      (node (ref "IC2") (pin "1") (pinfunction "SH/~{LD}_1") (pintype "input"))
    )
    (net (code "428") (name "~{SSER}") (class "Default")
      (node (ref "IC17") (pin "13") (pinfunction "A2_13") (pintype "input"))
      (node (ref "IC18") (pin "9") (pinfunction "QH_9") (pintype "output"))
    )
  )
)
